# wuBaseV1_4PH.net
KiCad netlist of a schematic drawn in EAGLE
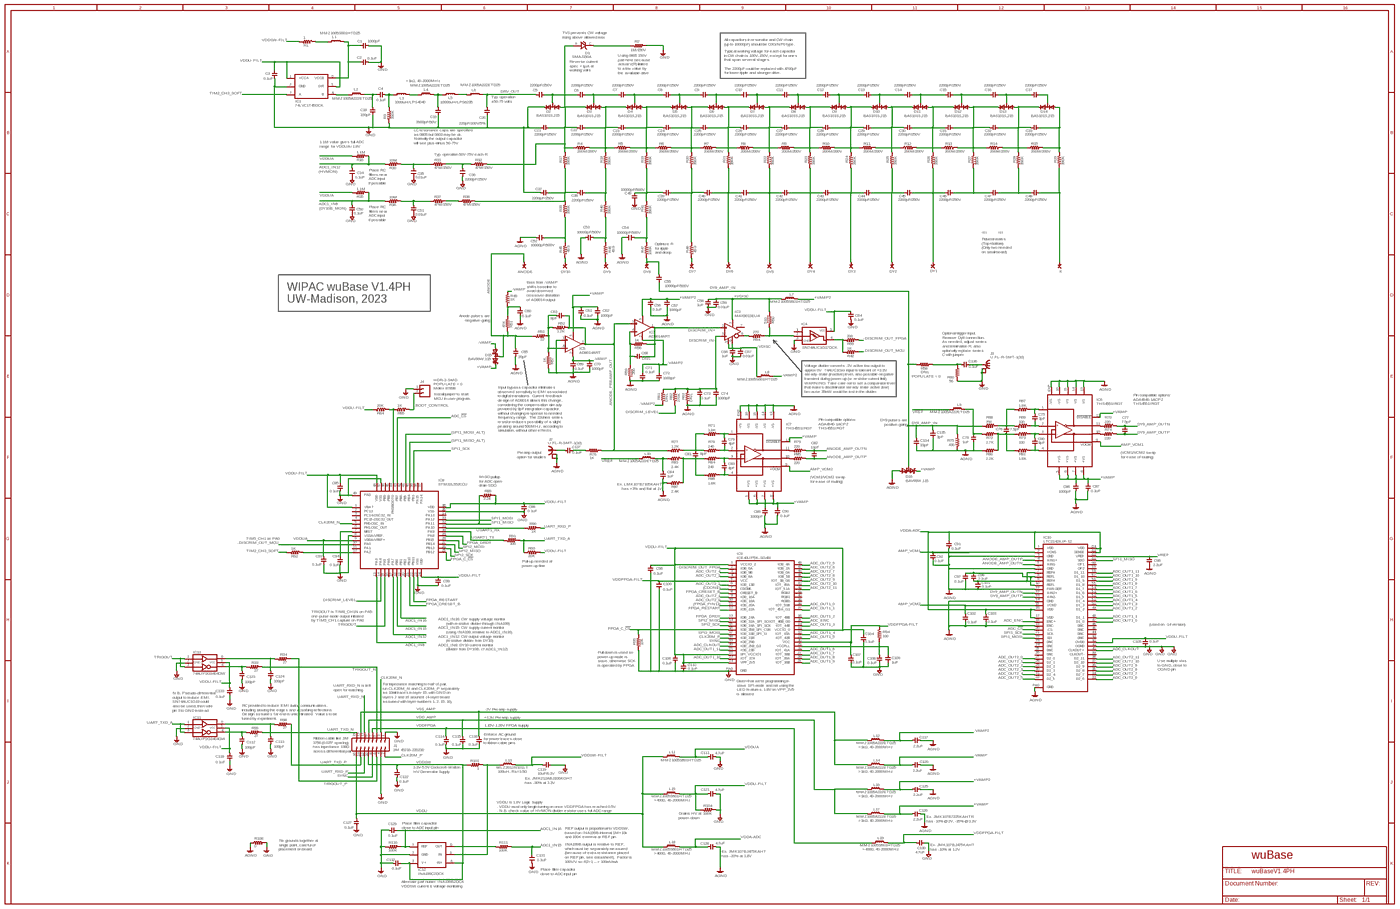
[diagram p0: schematic, sheet 1, overview]
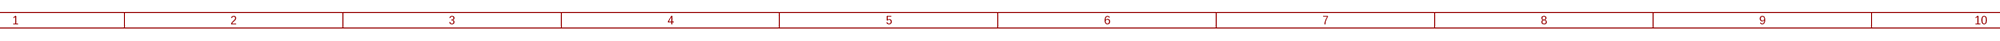
[diagram p1: schematic, sheet 1, part 1 of 4]
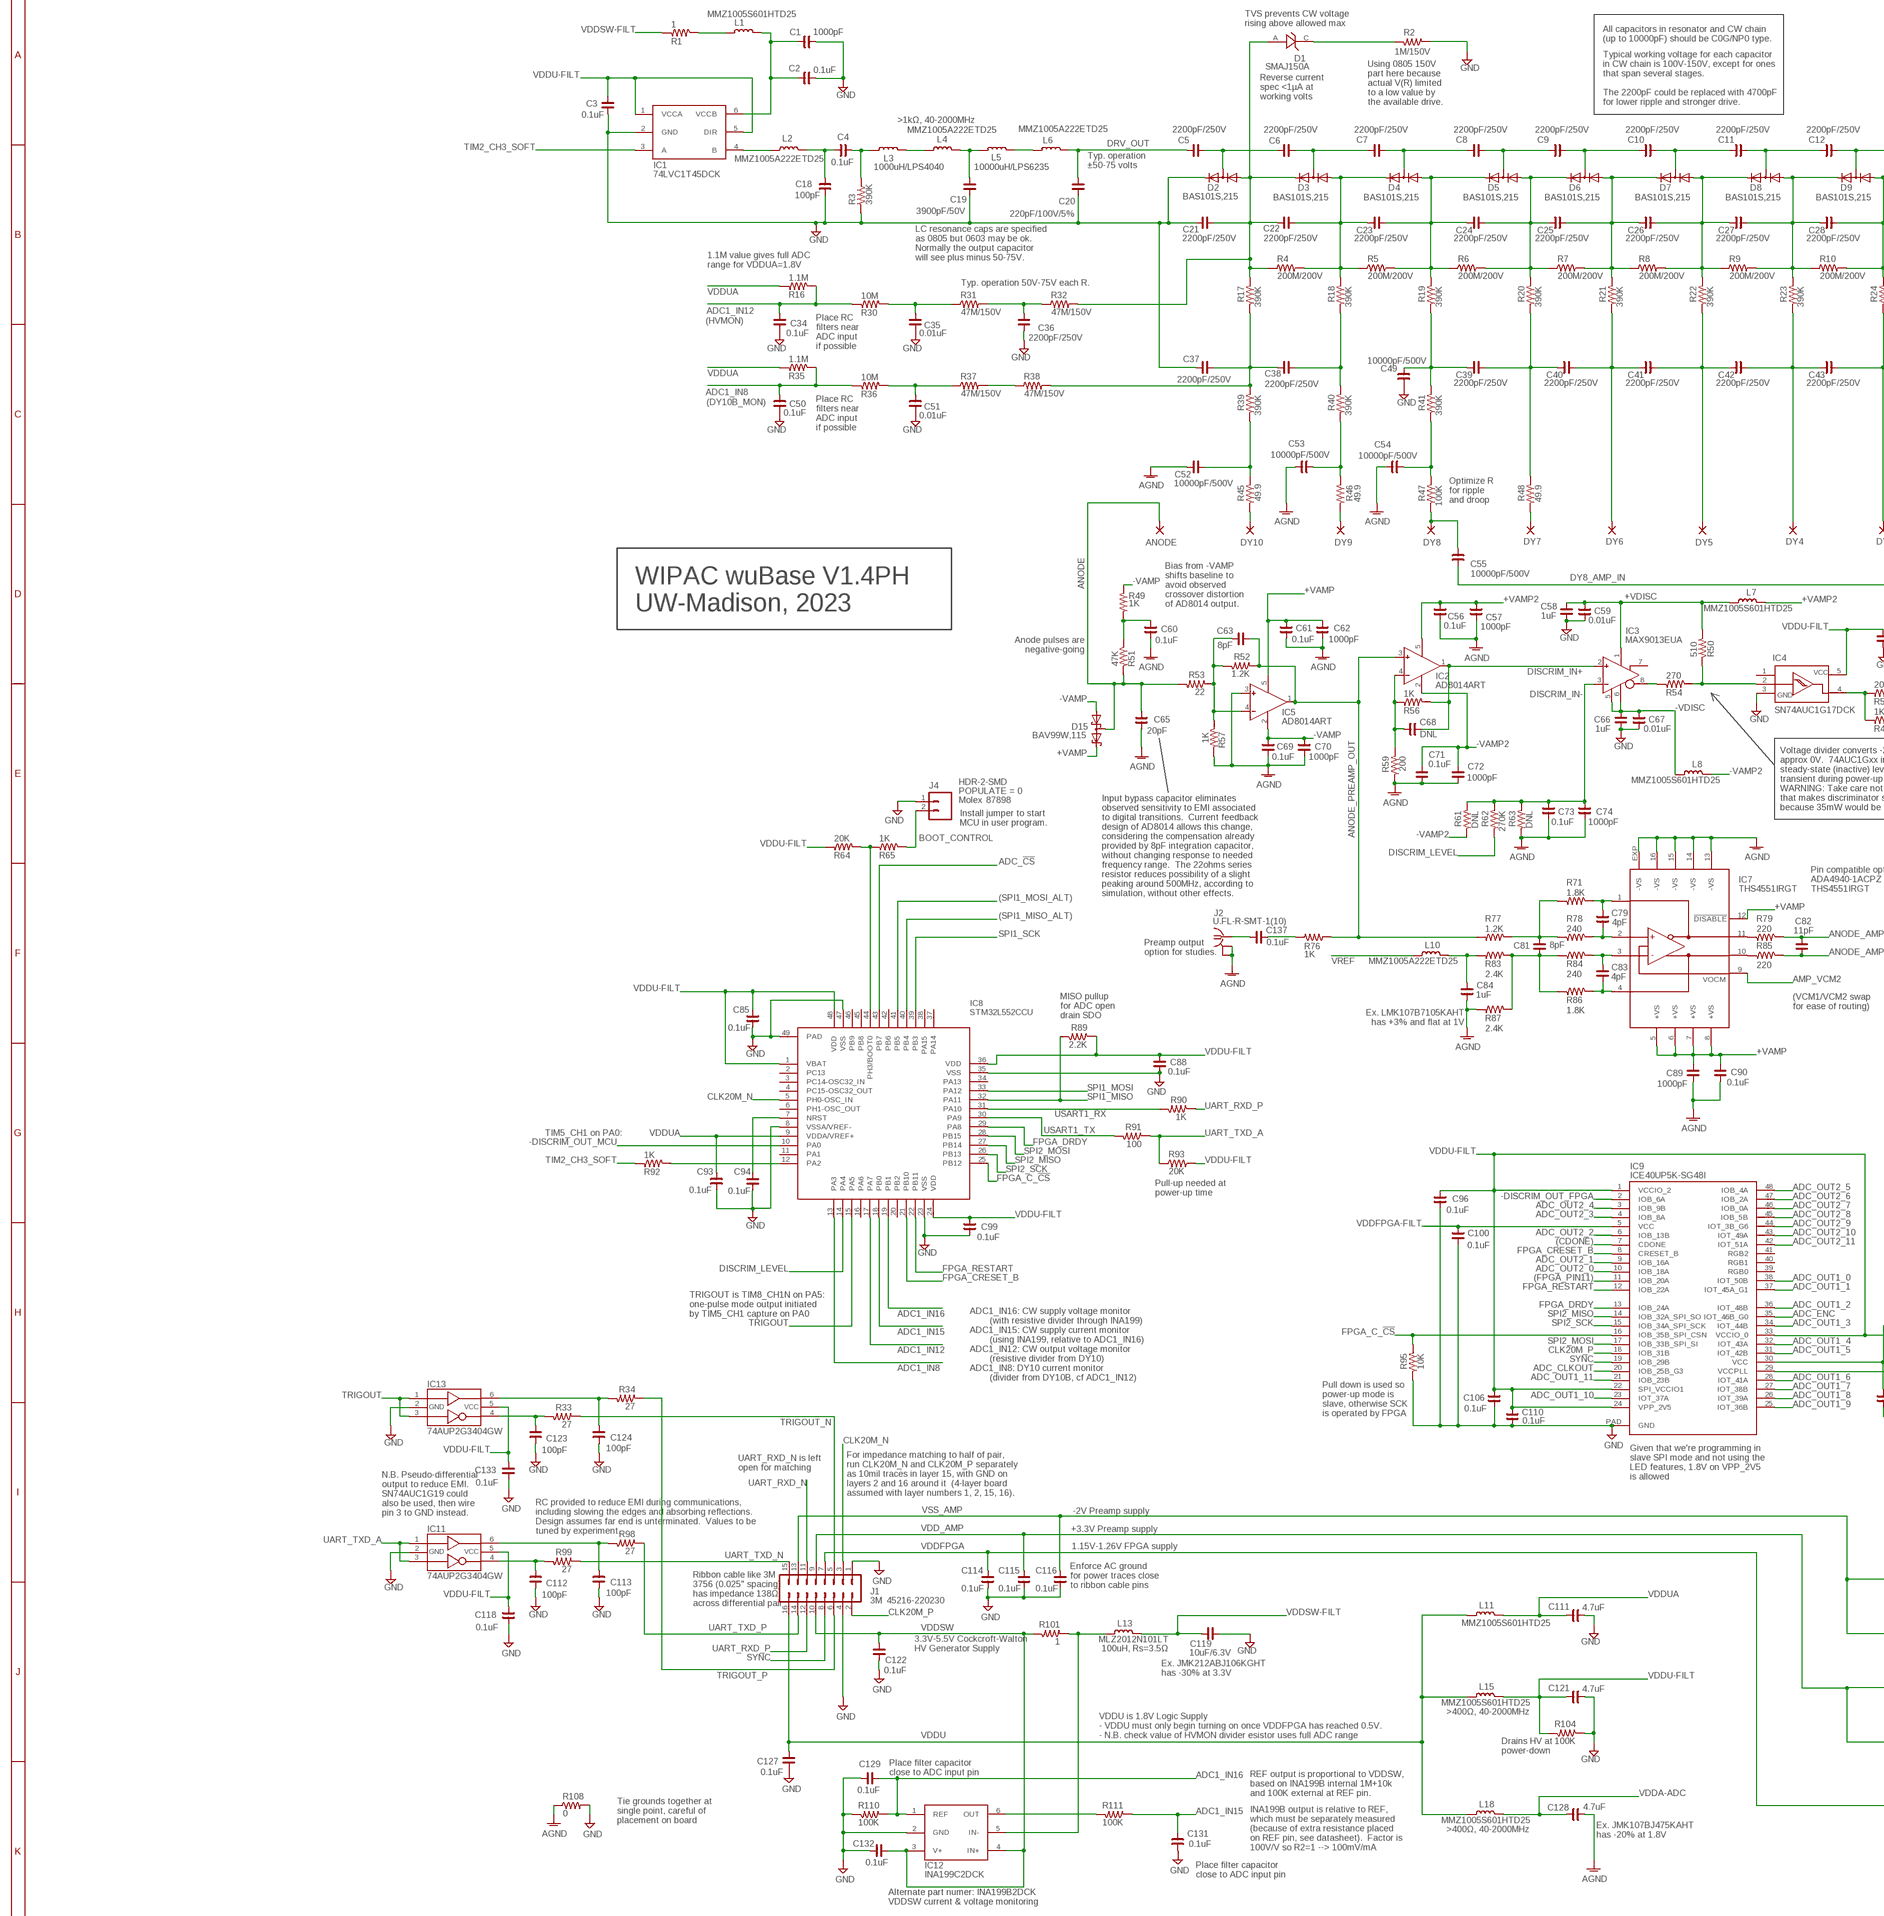
[diagram p2: schematic, sheet 1, part 2 of 4]
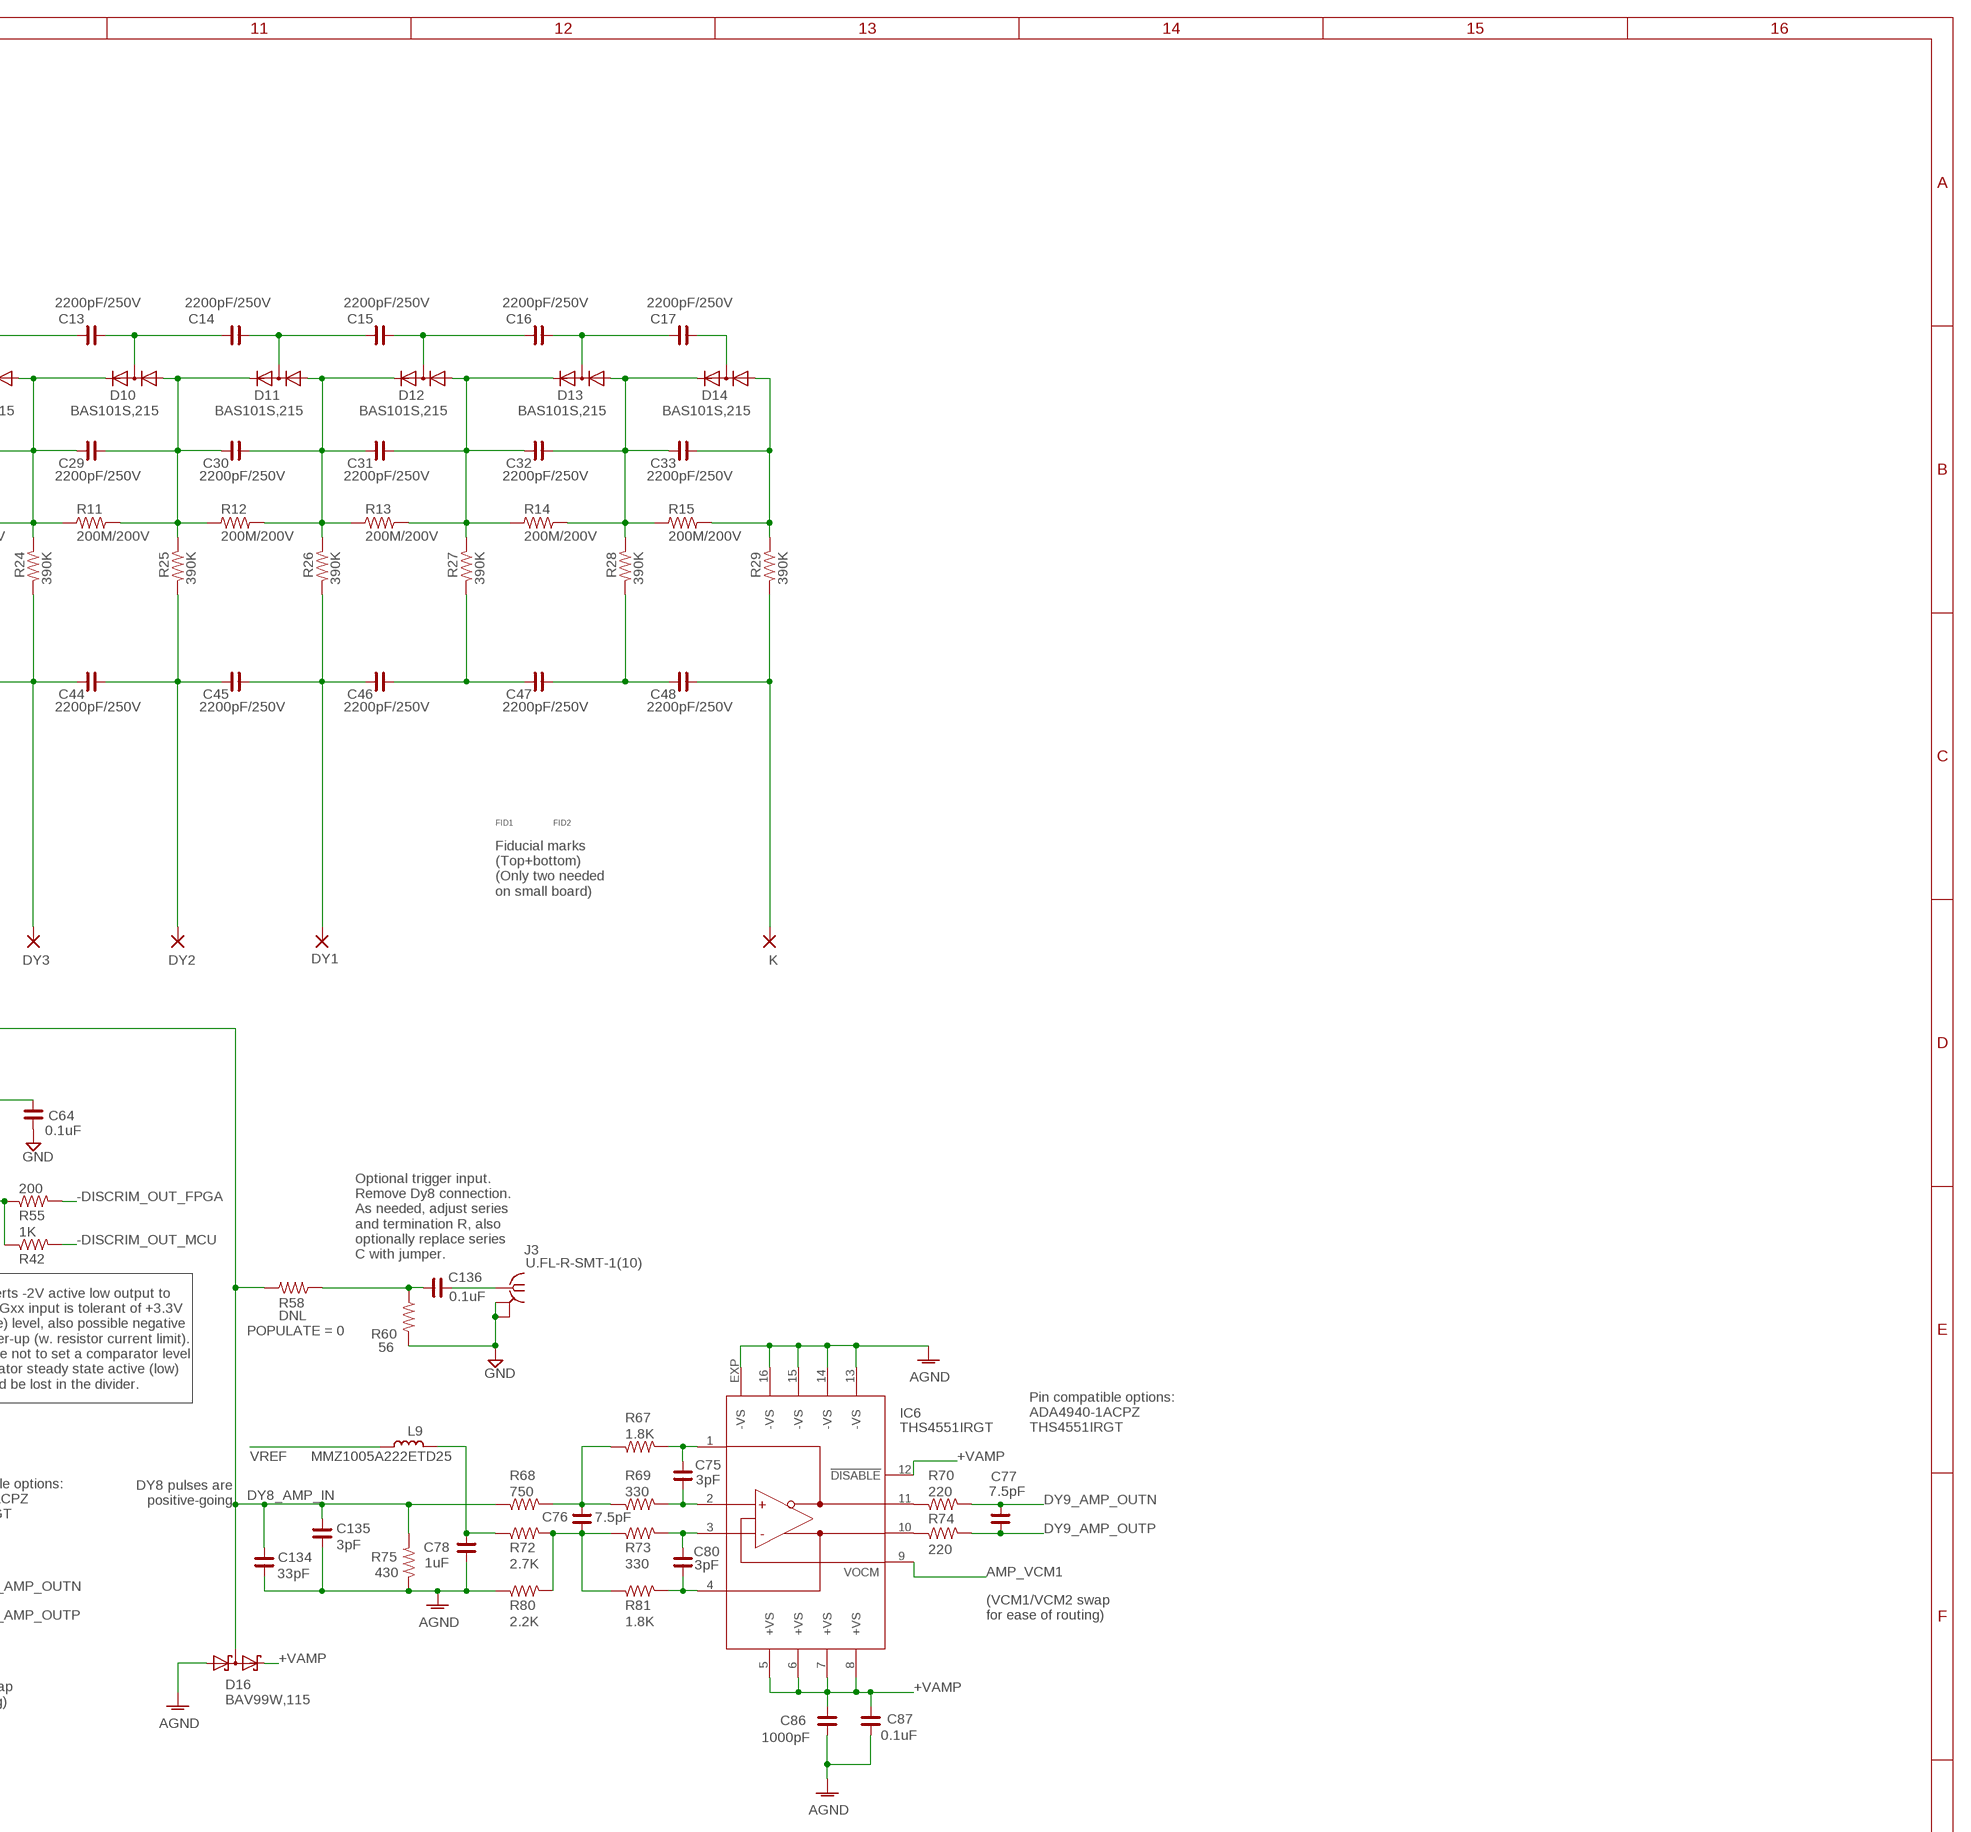
[diagram p3: schematic, sheet 1, part 3 of 4]
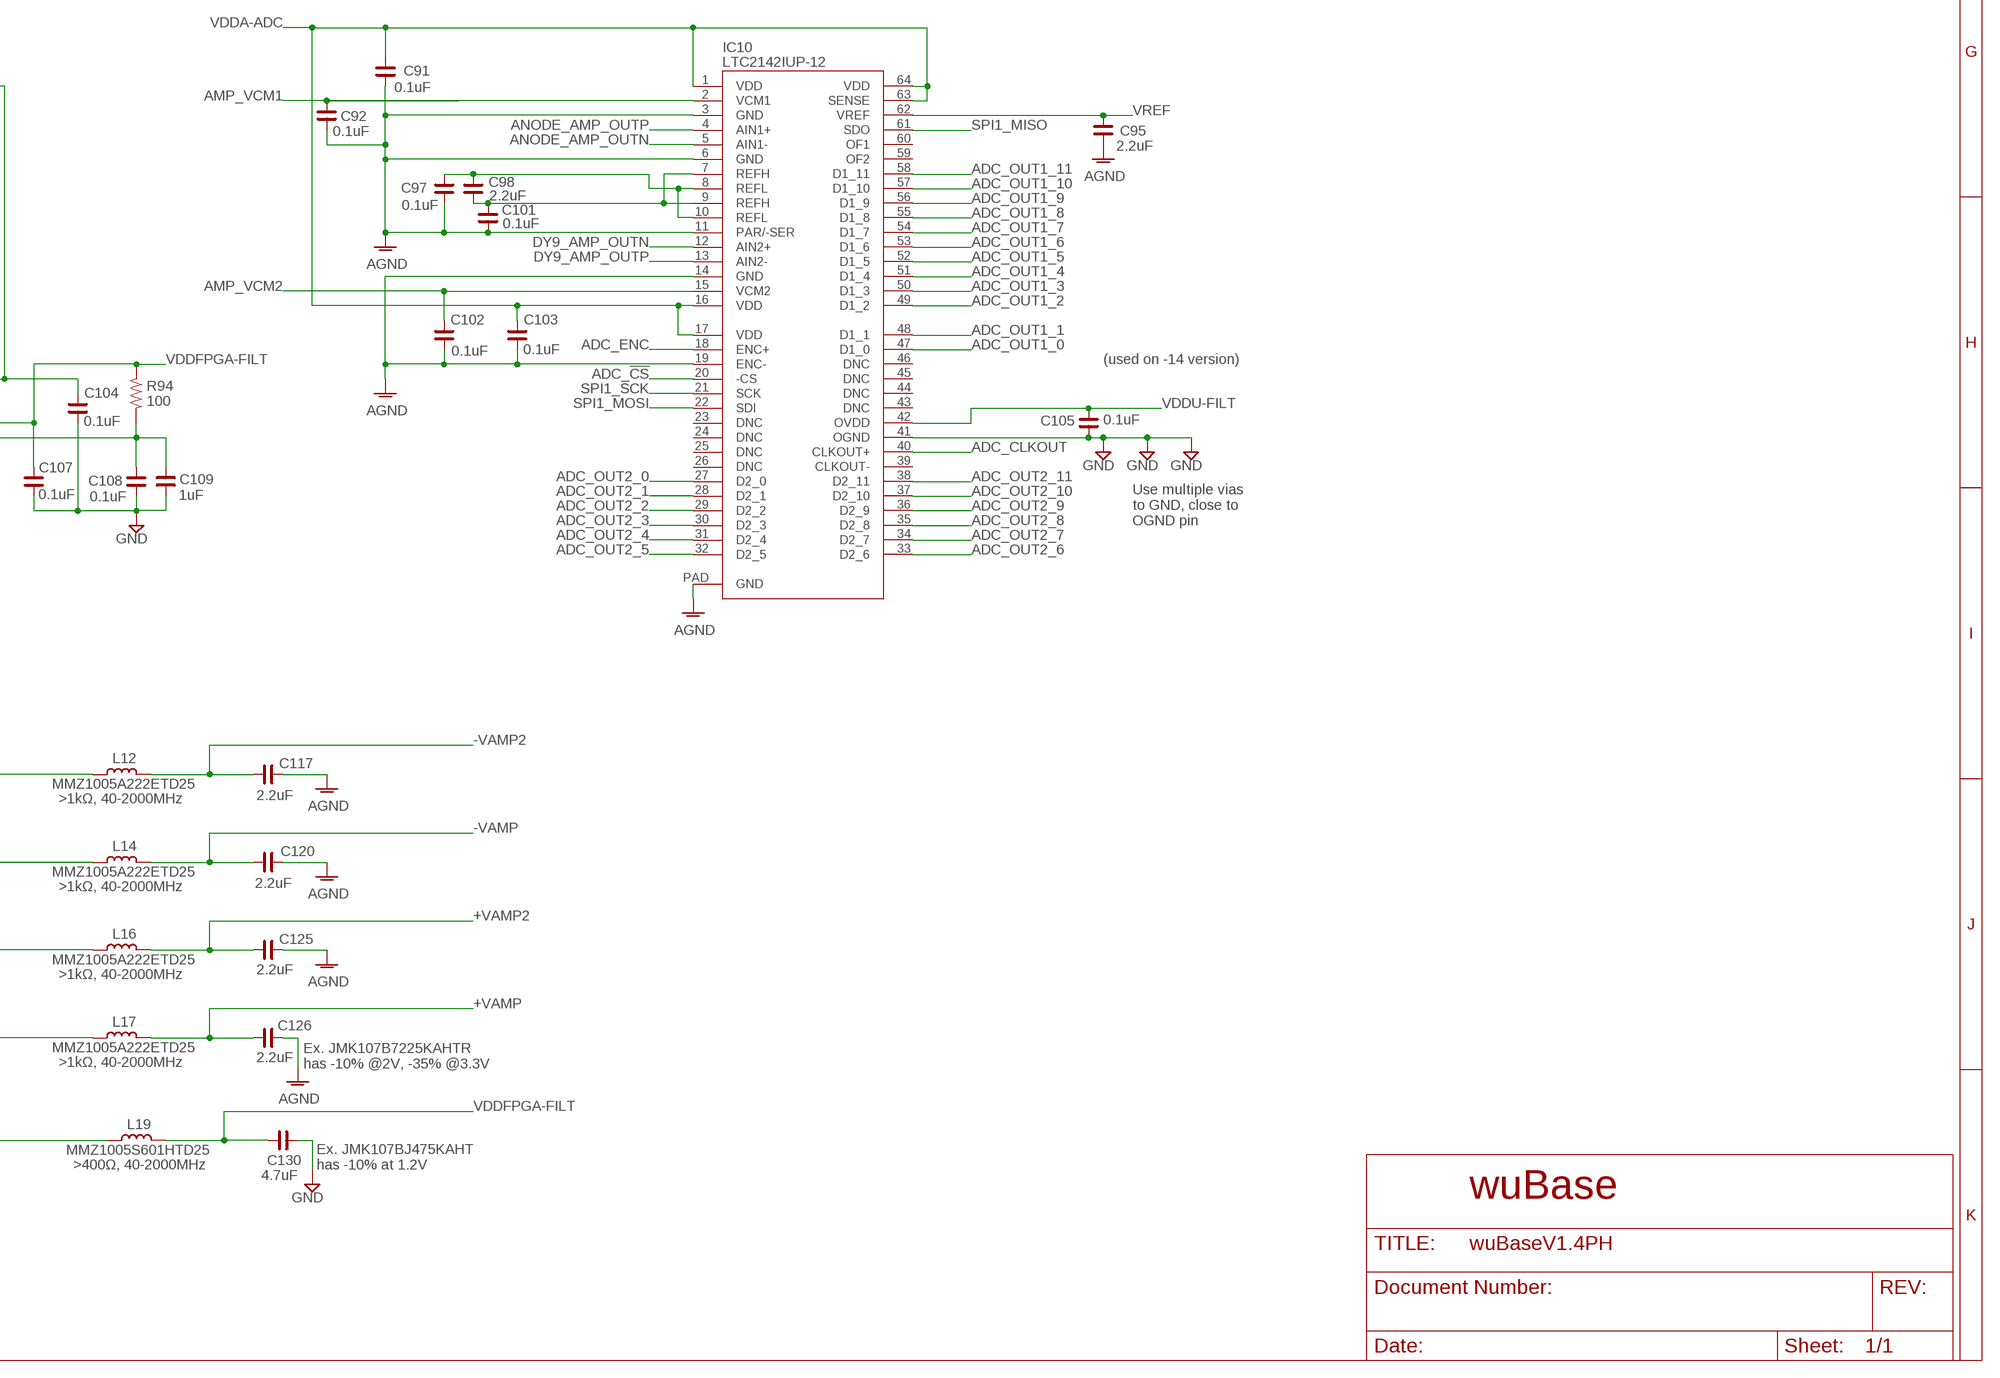
[diagram p4: schematic, sheet 1, part 4 of 4]

(export (version "E")
  (design (tool "Eeschema 10.0.6"))
  (components
    (comp (ref "ANODE")
      (value "PAD-0430-BARE")
      (footprint "eagle-import:0430-BARE")
      (libsource (lib "eagle-import") (part "PAD-0430-BARE"))
    )
    (comp (ref "C1")
      (value "1000pF")
      (footprint "eagle-import:C0402")
      (fields (field (name "MPN") "GCM155R71H102KA37D"))
      (libsource (lib "eagle-import") (part "C_0402"))
    )
    (comp (ref "C2")
      (value "0.1uF")
      (footprint "eagle-import:C0402")
      (fields (field (name "MPN") "GCM155R71C104KA55D"))
      (libsource (lib "eagle-import") (part "C_0402"))
    )
    (comp (ref "C3")
      (value "0.1uF")
      (footprint "eagle-import:C0402")
      (fields (field (name "MPN") "GCM155R71C104KA55D"))
      (libsource (lib "eagle-import") (part "C_0402"))
    )
    (comp (ref "C4")
      (value "0.1uF")
      (footprint "eagle-import:C0402-HV")
      (fields (field (name "MPN") "GCM155R71C104KA55D"))
      (libsource (lib "eagle-import") (part "C_0402HV"))
    )
    (comp (ref "C5")
      (value "2200pF/250V")
      (footprint "eagle-import:C0805-HV")
      (fields (field (name "MPN") "C0805C222JAGACAUTO"))
      (libsource (lib "eagle-import") (part "C_0805HV"))
    )
    (comp (ref "C6")
      (value "2200pF/250V")
      (footprint "eagle-import:C0805-HV")
      (fields (field (name "MPN") "C0805C222JAGACAUTO"))
      (libsource (lib "eagle-import") (part "C_0805HV"))
    )
    (comp (ref "C7")
      (value "2200pF/250V")
      (footprint "eagle-import:C0805-HV")
      (fields (field (name "MPN") "C0805C222JAGACAUTO"))
      (libsource (lib "eagle-import") (part "C_0805HV"))
    )
    (comp (ref "C8")
      (value "2200pF/250V")
      (footprint "eagle-import:C0805-HV")
      (fields (field (name "MPN") "C0805C222JAGACAUTO"))
      (libsource (lib "eagle-import") (part "C_0805HV"))
    )
    (comp (ref "C9")
      (value "2200pF/250V")
      (footprint "eagle-import:C0805-HV")
      (fields (field (name "MPN") "C0805C222JAGACAUTO"))
      (libsource (lib "eagle-import") (part "C_0805HV"))
    )
    (comp (ref "C10")
      (value "2200pF/250V")
      (footprint "eagle-import:C0805-HV")
      (fields (field (name "MPN") "C0805C222JAGACAUTO"))
      (libsource (lib "eagle-import") (part "C_0805HV"))
    )
    (comp (ref "C11")
      (value "2200pF/250V")
      (footprint "eagle-import:C0805-HV")
      (fields (field (name "MPN") "C0805C222JAGACAUTO"))
      (libsource (lib "eagle-import") (part "C_0805HV"))
    )
    (comp (ref "C12")
      (value "2200pF/250V")
      (footprint "eagle-import:C0805-HV")
      (fields (field (name "MPN") "C0805C222JAGACAUTO"))
      (libsource (lib "eagle-import") (part "C_0805HV"))
    )
    (comp (ref "C13")
      (value "2200pF/250V")
      (footprint "eagle-import:C0805-HV")
      (fields (field (name "MPN") "C0805C222JAGACAUTO"))
      (libsource (lib "eagle-import") (part "C_0805HV"))
    )
    (comp (ref "C14")
      (value "2200pF/250V")
      (footprint "eagle-import:C0805-HV")
      (fields (field (name "MPN") "C0805C222JAGACAUTO"))
      (libsource (lib "eagle-import") (part "C_0805HV"))
    )
    (comp (ref "C15")
      (value "2200pF/250V")
      (footprint "eagle-import:C0805-HV")
      (fields (field (name "MPN") "C0805C222JAGACAUTO"))
      (libsource (lib "eagle-import") (part "C_0805HV"))
    )
    (comp (ref "C16")
      (value "2200pF/250V")
      (footprint "eagle-import:C0805-HV")
      (fields (field (name "MPN") "C0805C222JAGACAUTO"))
      (libsource (lib "eagle-import") (part "C_0805HV"))
    )
    (comp (ref "C17")
      (value "2200pF/250V")
      (footprint "eagle-import:C0805-HV")
      (fields (field (name "MPN") "C0805C222JAGACAUTO"))
      (libsource (lib "eagle-import") (part "C_0805HV"))
    )
    (comp (ref "C18")
      (value "100pF")
      (footprint "eagle-import:C0402-HV")
      (fields (field (name "MPN") "C0402C101J3GACAUTO"))
      (libsource (lib "eagle-import") (part "C_0402HV"))
    )
    (comp (ref "C19")
      (value "3900pF/50V")
      (footprint "eagle-import:C0805-HV")
      (fields (field (name "MPN") "CGA4C2C0G1H392J060AA"))
      (libsource (lib "eagle-import") (part "C_0805HV"))
    )
    (comp (ref "C20")
      (value "220pF/100V/5%")
      (footprint "eagle-import:C0805-HV")
      (fields (field (name "MPN") "C0805C221J1GACAUTO"))
      (libsource (lib "eagle-import") (part "C_0805HV"))
    )
    (comp (ref "C21")
      (value "2200pF/250V")
      (footprint "eagle-import:C0805-HV")
      (fields (field (name "MPN") "C0805C222JAGACAUTO"))
      (libsource (lib "eagle-import") (part "C_0805HV"))
    )
    (comp (ref "C22")
      (value "2200pF/250V")
      (footprint "eagle-import:C0805-HV")
      (fields (field (name "MPN") "C0805C222JAGACAUTO"))
      (libsource (lib "eagle-import") (part "C_0805HV"))
    )
    (comp (ref "C23")
      (value "2200pF/250V")
      (footprint "eagle-import:C0805-HV")
      (fields (field (name "MPN") "C0805C222JAGACAUTO"))
      (libsource (lib "eagle-import") (part "C_0805HV"))
    )
    (comp (ref "C24")
      (value "2200pF/250V")
      (footprint "eagle-import:C0805-HV")
      (fields (field (name "MPN") "C0805C222JAGACAUTO"))
      (libsource (lib "eagle-import") (part "C_0805HV"))
    )
    (comp (ref "C25")
      (value "2200pF/250V")
      (footprint "eagle-import:C0805-HV")
      (fields (field (name "MPN") "C0805C222JAGACAUTO"))
      (libsource (lib "eagle-import") (part "C_0805HV"))
    )
    (comp (ref "C26")
      (value "2200pF/250V")
      (footprint "eagle-import:C0805-HV")
      (fields (field (name "MPN") "C0805C222JAGACAUTO"))
      (libsource (lib "eagle-import") (part "C_0805HV"))
    )
    (comp (ref "C27")
      (value "2200pF/250V")
      (footprint "eagle-import:C0805-HV")
      (fields (field (name "MPN") "C0805C222JAGACAUTO"))
      (libsource (lib "eagle-import") (part "C_0805HV"))
    )
    (comp (ref "C28")
      (value "2200pF/250V")
      (footprint "eagle-import:C0805-HV")
      (fields (field (name "MPN") "C0805C222JAGACAUTO"))
      (libsource (lib "eagle-import") (part "C_0805HV"))
    )
    (comp (ref "C29")
      (value "2200pF/250V")
      (footprint "eagle-import:C0805-HV")
      (fields (field (name "MPN") "C0805C222JAGACAUTO"))
      (libsource (lib "eagle-import") (part "C_0805HV"))
    )
    (comp (ref "C30")
      (value "2200pF/250V")
      (footprint "eagle-import:C0805-HV")
      (fields (field (name "MPN") "C0805C222JAGACAUTO"))
      (libsource (lib "eagle-import") (part "C_0805HV"))
    )
    (comp (ref "C31")
      (value "2200pF/250V")
      (footprint "eagle-import:C0805-HV")
      (fields (field (name "MPN") "C0805C222JAGACAUTO"))
      (libsource (lib "eagle-import") (part "C_0805HV"))
    )
    (comp (ref "C32")
      (value "2200pF/250V")
      (footprint "eagle-import:C0805-HV")
      (fields (field (name "MPN") "C0805C222JAGACAUTO"))
      (libsource (lib "eagle-import") (part "C_0805HV"))
    )
    (comp (ref "C33")
      (value "2200pF/250V")
      (footprint "eagle-import:C0805-HV")
      (fields (field (name "MPN") "C0805C222JAGACAUTO"))
      (libsource (lib "eagle-import") (part "C_0805HV"))
    )
    (comp (ref "C34")
      (value "0.1uF")
      (footprint "eagle-import:C0402")
      (fields (field (name "MPN") "GCM155R71C104KA55D"))
      (libsource (lib "eagle-import") (part "C_0402"))
    )
    (comp (ref "C35")
      (value "0.01uF")
      (footprint "eagle-import:C0402")
      (fields (field (name "MPN") "CGA2B2X5R1E103K050BA"))
      (libsource (lib "eagle-import") (part "C_0402"))
    )
    (comp (ref "C36")
      (value "2200pF/250V")
      (footprint "eagle-import:C0805-HV")
      (fields (field (name "MPN") "C0805C222JAGACAUTO"))
      (libsource (lib "eagle-import") (part "C_0805HV"))
    )
    (comp (ref "C37")
      (value "2200pF/250V")
      (footprint "eagle-import:C0805-HV")
      (fields (field (name "MPN") "C0805C222JAGACAUTO"))
      (libsource (lib "eagle-import") (part "C_0805HV"))
    )
    (comp (ref "C38")
      (value "2200pF/250V")
      (footprint "eagle-import:C0805-HV")
      (fields (field (name "MPN") "C0805C222JAGACAUTO"))
      (libsource (lib "eagle-import") (part "C_0805HV"))
    )
    (comp (ref "C39")
      (value "2200pF/250V")
      (footprint "eagle-import:C0805-HV")
      (fields (field (name "MPN") "C0805C222JAGACAUTO"))
      (libsource (lib "eagle-import") (part "C_0805HV"))
    )
    (comp (ref "C40")
      (value "2200pF/250V")
      (footprint "eagle-import:C0805-HV")
      (fields (field (name "MPN") "C0805C222JAGACAUTO"))
      (libsource (lib "eagle-import") (part "C_0805HV"))
    )
    (comp (ref "C41")
      (value "2200pF/250V")
      (footprint "eagle-import:C0805-HV")
      (fields (field (name "MPN") "C0805C222JAGACAUTO"))
      (libsource (lib "eagle-import") (part "C_0805HV"))
    )
    (comp (ref "C42")
      (value "2200pF/250V")
      (footprint "eagle-import:C0805-HV")
      (fields (field (name "MPN") "C0805C222JAGACAUTO"))
      (libsource (lib "eagle-import") (part "C_0805HV"))
    )
    (comp (ref "C43")
      (value "2200pF/250V")
      (footprint "eagle-import:C0805-HV")
      (fields (field (name "MPN") "C0805C222JAGACAUTO"))
      (libsource (lib "eagle-import") (part "C_0805HV"))
    )
    (comp (ref "C44")
      (value "2200pF/250V")
      (footprint "eagle-import:C0805-HV")
      (fields (field (name "MPN") "C0805C222JAGACAUTO"))
      (libsource (lib "eagle-import") (part "C_0805HV"))
    )
    (comp (ref "C45")
      (value "2200pF/250V")
      (footprint "eagle-import:C0805-HV")
      (fields (field (name "MPN") "C0805C222JAGACAUTO"))
      (libsource (lib "eagle-import") (part "C_0805HV"))
    )
    (comp (ref "C46")
      (value "2200pF/250V")
      (footprint "eagle-import:C0805-HV")
      (fields (field (name "MPN") "C0805C222JAGACAUTO"))
      (libsource (lib "eagle-import") (part "C_0805HV"))
    )
    (comp (ref "C47")
      (value "2200pF/250V")
      (footprint "eagle-import:C0805-HV")
      (fields (field (name "MPN") "C0805C222JAGACAUTO"))
      (libsource (lib "eagle-import") (part "C_0805HV"))
    )
    (comp (ref "C48")
      (value "2200pF/250V")
      (footprint "eagle-import:C0805-HV")
      (fields (field (name "MPN") "C0805C222JAGACAUTO"))
      (libsource (lib "eagle-import") (part "C_0805HV"))
    )
    (comp (ref "C49")
      (value "10000pF/500V")
      (footprint "eagle-import:C1206-HV")
      (fields (field (name "MPN") "CGA5L4NP02J103J160AA"))
      (libsource (lib "eagle-import") (part "C_1206HV"))
    )
    (comp (ref "C50")
      (value "0.1uF")
      (footprint "eagle-import:C0402")
      (fields (field (name "MPN") "GCM155R71C104KA55D"))
      (libsource (lib "eagle-import") (part "C_0402"))
    )
    (comp (ref "C51")
      (value "0.01uF")
      (footprint "eagle-import:C0402")
      (fields (field (name "MPN") "CGA2B2X5R1E103K050BA"))
      (libsource (lib "eagle-import") (part "C_0402"))
    )
    (comp (ref "C52")
      (value "10000pF/500V")
      (footprint "eagle-import:C1206-HV")
      (fields (field (name "MPN") "CGA5L4NP02J103J160AA"))
      (libsource (lib "eagle-import") (part "C_1206HV"))
    )
    (comp (ref "C53")
      (value "10000pF/500V")
      (footprint "eagle-import:C1206-HV")
      (fields (field (name "MPN") "CGA5L4NP02J103J160AA"))
      (libsource (lib "eagle-import") (part "C_1206HV"))
    )
    (comp (ref "C54")
      (value "10000pF/500V")
      (footprint "eagle-import:C1206-HV")
      (fields (field (name "MPN") "CGA5L4NP02J103J160AA"))
      (libsource (lib "eagle-import") (part "C_1206HV"))
    )
    (comp (ref "C55")
      (value "10000pF/500V")
      (footprint "eagle-import:C1206-HV")
      (fields (field (name "MPN") "CGA5L4NP02J103J160AA"))
      (libsource (lib "eagle-import") (part "C_1206HV"))
    )
    (comp (ref "C56")
      (value "0.1uF")
      (footprint "eagle-import:C0402")
      (fields (field (name "MPN") "GCM155R71C104KA55D"))
      (libsource (lib "eagle-import") (part "C_0402"))
    )
    (comp (ref "C57")
      (value "1000pF")
      (footprint "eagle-import:C0402")
      (fields (field (name "MPN") "GCM155R71H102KA37D"))
      (libsource (lib "eagle-import") (part "C_0402"))
    )
    (comp (ref "C58")
      (value "1uF")
      (footprint "eagle-import:C0603")
      (fields (field (name "MPN") "LMK107B7105KAHT"))
      (libsource (lib "eagle-import") (part "C_0603"))
    )
    (comp (ref "C59")
      (value "0.01uF")
      (footprint "eagle-import:C0402")
      (fields (field (name "MPN") "CGA2B2X5R1E103K050BA"))
      (libsource (lib "eagle-import") (part "C_0402"))
    )
    (comp (ref "C60")
      (value "0.1uF")
      (footprint "eagle-import:C0402")
      (fields (field (name "MPN") "GCM155R71C104KA55D"))
      (libsource (lib "eagle-import") (part "C_0402"))
    )
    (comp (ref "C61")
      (value "0.1uF")
      (footprint "eagle-import:C0402")
      (fields (field (name "MPN") "GCM155R71C104KA55D"))
      (libsource (lib "eagle-import") (part "C_0402"))
    )
    (comp (ref "C62")
      (value "1000pF")
      (footprint "eagle-import:C0402")
      (fields (field (name "MPN") "GCM155R71H102KA37D"))
      (libsource (lib "eagle-import") (part "C_0402"))
    )
    (comp (ref "C63")
      (value "8pF")
      (footprint "eagle-import:C0402")
      (fields (field (name "MPN") "GCM1555C1H8R0BA16D"))
      (libsource (lib "eagle-import") (part "C_0402"))
    )
    (comp (ref "C64")
      (value "0.1uF")
      (footprint "eagle-import:C0402")
      (fields (field (name "MPN") "GCM155R71C104KA55D"))
      (libsource (lib "eagle-import") (part "C_0402"))
    )
    (comp (ref "C65")
      (value "20pF")
      (footprint "eagle-import:C0402")
      (fields (field (name "MPN") "GCM1555C1H200JA16D"))
      (libsource (lib "eagle-import") (part "C_0402"))
    )
    (comp (ref "C66")
      (value "1uF")
      (footprint "eagle-import:C0603")
      (fields (field (name "MPN") "LMK107B7105KAHT"))
      (libsource (lib "eagle-import") (part "C_0603"))
    )
    (comp (ref "C67")
      (value "0.01uF")
      (footprint "eagle-import:C0402")
      (fields (field (name "MPN") "CGA2B2X5R1E103K050BA"))
      (libsource (lib "eagle-import") (part "C_0402"))
    )
    (comp (ref "C68")
      (value "DNL")
      (footprint "eagle-import:C0402")
      (fields (field (name "POPULATE") "0"))
      (libsource (lib "eagle-import") (part "C_0402"))
    )
    (comp (ref "C69")
      (value "0.1uF")
      (footprint "eagle-import:C0402")
      (fields (field (name "MPN") "GCM155R71C104KA55D"))
      (libsource (lib "eagle-import") (part "C_0402"))
    )
    (comp (ref "C70")
      (value "1000pF")
      (footprint "eagle-import:C0402")
      (fields (field (name "MPN") "GCM155R71H102KA37D"))
      (libsource (lib "eagle-import") (part "C_0402"))
    )
    (comp (ref "C71")
      (value "0.1uF")
      (footprint "eagle-import:C0402")
      (fields (field (name "MPN") "GCM155R71C104KA55D"))
      (libsource (lib "eagle-import") (part "C_0402"))
    )
    (comp (ref "C72")
      (value "1000pF")
      (footprint "eagle-import:C0402")
      (fields (field (name "MPN") "GCM155R71H102KA37D"))
      (libsource (lib "eagle-import") (part "C_0402"))
    )
    (comp (ref "C73")
      (value "0.1uF")
      (footprint "eagle-import:C0402")
      (fields (field (name "MPN") "GCM155R71C104KA55D"))
      (libsource (lib "eagle-import") (part "C_0402"))
    )
    (comp (ref "C74")
      (value "1000pF")
      (footprint "eagle-import:C0402")
      (fields (field (name "MPN") "GCM155R71H102KA37D"))
      (libsource (lib "eagle-import") (part "C_0402"))
    )
    (comp (ref "C75")
      (value "3pF")
      (footprint "eagle-import:C0402")
      (fields (field (name "MPN") "GCM1555C1H3R0BA16D"))
      (libsource (lib "eagle-import") (part "C_0402"))
    )
    (comp (ref "C76")
      (value "7.5pF")
      (footprint "eagle-import:C0402")
      (fields (field (name "MPN") "GCQ1555C1H7R5BB01D"))
      (libsource (lib "eagle-import") (part "C_0402"))
    )
    (comp (ref "C77")
      (value "7.5pF")
      (footprint "eagle-import:C0402")
      (fields (field (name "MPN") "GCQ1555C1H7R5BB01D"))
      (libsource (lib "eagle-import") (part "C_0402"))
    )
    (comp (ref "C78")
      (value "1uF")
      (footprint "eagle-import:C0603")
      (fields (field (name "MPN") "LMK107B7105KAHT"))
      (libsource (lib "eagle-import") (part "C_0603"))
    )
    (comp (ref "C79")
      (value "4pF")
      (footprint "eagle-import:C0402")
      (fields (field (name "MPN") "GCM1555C1H4R0BA16D"))
      (libsource (lib "eagle-import") (part "C_0402"))
    )
    (comp (ref "C80")
      (value "3pF")
      (footprint "eagle-import:C0402")
      (fields (field (name "MPN") "GCM1555C1H3R0BA16D"))
      (libsource (lib "eagle-import") (part "C_0402"))
    )
    (comp (ref "C81")
      (value "8pF")
      (footprint "eagle-import:C0402")
      (fields (field (name "MPN") "GCM1555C1H8R0BA16D"))
      (libsource (lib "eagle-import") (part "C_0402"))
    )
    (comp (ref "C82")
      (value "11pF")
      (footprint "eagle-import:C0402")
      (fields (field (name "MPN") "GCM1555C1H110FA16D"))
      (libsource (lib "eagle-import") (part "C_0402"))
    )
    (comp (ref "C83")
      (value "4pF")
      (footprint "eagle-import:C0402")
      (fields (field (name "MPN") "GCM1555C1H4R0BA16D"))
      (libsource (lib "eagle-import") (part "C_0402"))
    )
    (comp (ref "C84")
      (value "1uF")
      (footprint "eagle-import:C0603")
      (fields (field (name "MPN") "LMK107B7105KAHT"))
      (libsource (lib "eagle-import") (part "C_0603"))
    )
    (comp (ref "C85")
      (value "0.1uF")
      (footprint "eagle-import:C0402")
      (fields (field (name "MPN") "GCM155R71C104KA55D"))
      (libsource (lib "eagle-import") (part "C_0402"))
    )
    (comp (ref "C86")
      (value "1000pF")
      (footprint "eagle-import:C0402")
      (fields (field (name "MPN") "GCM155R71H102KA37D"))
      (libsource (lib "eagle-import") (part "C_0402"))
    )
    (comp (ref "C87")
      (value "0.1uF")
      (footprint "eagle-import:C0402")
      (fields (field (name "MPN") "GCM155R71C104KA55D"))
      (libsource (lib "eagle-import") (part "C_0402"))
    )
    (comp (ref "C88")
      (value "0.1uF")
      (footprint "eagle-import:C0402")
      (fields (field (name "MPN") "GCM155R71C104KA55D"))
      (libsource (lib "eagle-import") (part "C_0402"))
    )
    (comp (ref "C89")
      (value "1000pF")
      (footprint "eagle-import:C0402")
      (fields (field (name "MPN") "GCM155R71H102KA37D"))
      (libsource (lib "eagle-import") (part "C_0402"))
    )
    (comp (ref "C90")
      (value "0.1uF")
      (footprint "eagle-import:C0402")
      (fields (field (name "MPN") "GCM155R71C104KA55D"))
      (libsource (lib "eagle-import") (part "C_0402"))
    )
    (comp (ref "C91")
      (value "0.1uF")
      (footprint "eagle-import:C0402")
      (fields (field (name "MPN") "GCM155R71C104KA55D"))
      (libsource (lib "eagle-import") (part "C_0402"))
    )
    (comp (ref "C92")
      (value "0.1uF")
      (footprint "eagle-import:C0402")
      (fields (field (name "MPN") "GCM155R71C104KA55D"))
      (libsource (lib "eagle-import") (part "C_0402"))
    )
    (comp (ref "C93")
      (value "0.1uF")
      (footprint "eagle-import:C0402")
      (fields (field (name "MPN") "GCM155R71C104KA55D"))
      (libsource (lib "eagle-import") (part "C_0402"))
    )
    (comp (ref "C94")
      (value "0.1uF")
      (footprint "eagle-import:C0402")
      (fields (field (name "MPN") "GCM155R71C104KA55D"))
      (libsource (lib "eagle-import") (part "C_0402"))
    )
    (comp (ref "C95")
      (value "2.2uF")
      (footprint "eagle-import:C0603")
      (fields (field (name "MPN") "CGA3E1X7R0J225K080AC"))
      (libsource (lib "eagle-import") (part "C_0603"))
    )
    (comp (ref "C96")
      (value "0.1uF")
      (footprint "eagle-import:C0402")
      (fields (field (name "MPN") "GCM155R71C104KA55D"))
      (libsource (lib "eagle-import") (part "C_0402"))
    )
    (comp (ref "C97")
      (value "0.1uF")
      (footprint "eagle-import:C0402")
      (fields (field (name "MPN") "GCM155R71C104KA55D"))
      (libsource (lib "eagle-import") (part "C_0402"))
    )
    (comp (ref "C98")
      (value "2.2uF")
      (footprint "eagle-import:C0603")
      (fields (field (name "MPN") "CGA3E1X7R0J225K080AC"))
      (libsource (lib "eagle-import") (part "C_0603"))
    )
    (comp (ref "C99")
      (value "0.1uF")
      (footprint "eagle-import:C0402")
      (fields (field (name "MPN") "GCM155R71C104KA55D"))
      (libsource (lib "eagle-import") (part "C_0402"))
    )
    (comp (ref "C100")
      (value "0.1uF")
      (footprint "eagle-import:C0402")
      (fields (field (name "MPN") "GCM155R71C104KA55D"))
      (libsource (lib "eagle-import") (part "C_0402"))
    )
    (comp (ref "C101")
      (value "0.1uF")
      (footprint "eagle-import:C0402")
      (fields (field (name "MPN") "GCM155R71C104KA55D"))
      (libsource (lib "eagle-import") (part "C_0402"))
    )
    (comp (ref "C102")
      (value "0.1uF")
      (footprint "eagle-import:C0402")
      (fields (field (name "MPN") "GCM155R71C104KA55D"))
      (libsource (lib "eagle-import") (part "C_0402"))
    )
    (comp (ref "C103")
      (value "0.1uF")
      (footprint "eagle-import:C0402")
      (fields (field (name "MPN") "GCM155R71C104KA55D"))
      (libsource (lib "eagle-import") (part "C_0402"))
    )
    (comp (ref "C104")
      (value "0.1uF")
      (footprint "eagle-import:C0402")
      (fields (field (name "MPN") "GCM155R71C104KA55D"))
      (libsource (lib "eagle-import") (part "C_0402"))
    )
    (comp (ref "C105")
      (value "0.1uF")
      (footprint "eagle-import:C0402")
      (fields (field (name "MPN") "GCM155R71C104KA55D"))
      (libsource (lib "eagle-import") (part "C_0402"))
    )
    (comp (ref "C106")
      (value "0.1uF")
      (footprint "eagle-import:C0402")
      (fields (field (name "MPN") "GCM155R71C104KA55D"))
      (libsource (lib "eagle-import") (part "C_0402"))
    )
    (comp (ref "C107")
      (value "0.1uF")
      (footprint "eagle-import:C0402")
      (fields (field (name "MPN") "GCM155R71C104KA55D"))
      (libsource (lib "eagle-import") (part "C_0402"))
    )
    (comp (ref "C108")
      (value "0.1uF")
      (footprint "eagle-import:C0402")
      (fields (field (name "MPN") "GCM155R71C104KA55D"))
      (libsource (lib "eagle-import") (part "C_0402"))
    )
    (comp (ref "C109")
      (value "1uF")
      (footprint "eagle-import:C0603")
      (fields (field (name "MPN") "LMK107B7105KAHT"))
      (libsource (lib "eagle-import") (part "C_0603"))
    )
    (comp (ref "C110")
      (value "0.1uF")
      (footprint "eagle-import:C0402")
      (fields (field (name "MPN") "GCM155R71C104KA55D"))
      (libsource (lib "eagle-import") (part "C_0402"))
    )
    (comp (ref "C111")
      (value "4.7uF")
      (footprint "eagle-import:C0603")
      (fields (field (name "MPN") "JMK107BJ475KAHT"))
      (libsource (lib "eagle-import") (part "C_0603"))
    )
    (comp (ref "C112")
      (value "100pF")
      (footprint "eagle-import:C0402")
      (fields (field (name "MPN") "C0402C101J3GACAUTO"))
      (libsource (lib "eagle-import") (part "C_0402"))
    )
    (comp (ref "C113")
      (value "100pF")
      (footprint "eagle-import:C0402")
      (fields (field (name "MPN") "C0402C101J3GACAUTO"))
      (libsource (lib "eagle-import") (part "C_0402"))
    )
    (comp (ref "C114")
      (value "0.1uF")
      (footprint "eagle-import:C0402")
      (fields (field (name "MPN") "GCM155R71C104KA55D"))
      (libsource (lib "eagle-import") (part "C_0402"))
    )
    (comp (ref "C115")
      (value "0.1uF")
      (footprint "eagle-import:C0402")
      (fields (field (name "MPN") "GCM155R71C104KA55D"))
      (libsource (lib "eagle-import") (part "C_0402"))
    )
    (comp (ref "C116")
      (value "0.1uF")
      (footprint "eagle-import:C0402")
      (fields (field (name "MPN") "GCM155R71C104KA55D"))
      (libsource (lib "eagle-import") (part "C_0402"))
    )
    (comp (ref "C117")
      (value "2.2uF")
      (footprint "eagle-import:C0603")
      (fields (field (name "MPN") "CGA3E1X7R0J225K080AC"))
      (libsource (lib "eagle-import") (part "C_0603"))
    )
    (comp (ref "C118")
      (value "0.1uF")
      (footprint "eagle-import:C0402")
      (fields (field (name "MPN") "GCM155R71C104KA55D"))
      (libsource (lib "eagle-import") (part "C_0402"))
    )
    (comp (ref "C119")
      (value "10uF/6.3V")
      (footprint "eagle-import:C0805")
      (fields (field (name "MPN") "C0805C106K8PACTU"))
      (libsource (lib "eagle-import") (part "C_0805"))
    )
    (comp (ref "C120")
      (value "2.2uF")
      (footprint "eagle-import:C0603")
      (fields (field (name "MPN") "CGA3E1X7R0J225K080AC"))
      (libsource (lib "eagle-import") (part "C_0603"))
    )
    (comp (ref "C121")
      (value "4.7uF")
      (footprint "eagle-import:C0603")
      (fields (field (name "MPN") "JMK107BJ475KAHT"))
      (libsource (lib "eagle-import") (part "C_0603"))
    )
    (comp (ref "C122")
      (value "0.1uF")
      (footprint "eagle-import:C0402")
      (fields (field (name "MPN") "GCM155R71C104KA55D"))
      (libsource (lib "eagle-import") (part "C_0402"))
    )
    (comp (ref "C123")
      (value "100pF")
      (footprint "eagle-import:C0402")
      (fields (field (name "MPN") "C0402C101J3GACAUTO"))
      (libsource (lib "eagle-import") (part "C_0402"))
    )
    (comp (ref "C124")
      (value "100pF")
      (footprint "eagle-import:C0402")
      (fields (field (name "MPN") "C0402C101J3GACAUTO"))
      (libsource (lib "eagle-import") (part "C_0402"))
    )
    (comp (ref "C125")
      (value "2.2uF")
      (footprint "eagle-import:C0603")
      (fields (field (name "MPN") "CGA3E1X7R0J225K080AC"))
      (libsource (lib "eagle-import") (part "C_0603"))
    )
    (comp (ref "C126")
      (value "2.2uF")
      (footprint "eagle-import:C0603")
      (fields (field (name "MPN") "CGA3E1X7R0J225K080AC"))
      (libsource (lib "eagle-import") (part "C_0603"))
    )
    (comp (ref "C127")
      (value "0.1uF")
      (footprint "eagle-import:C0402")
      (fields (field (name "MPN") "GCM155R71C104KA55D"))
      (libsource (lib "eagle-import") (part "C_0402"))
    )
    (comp (ref "C128")
      (value "4.7uF")
      (footprint "eagle-import:C0603")
      (fields (field (name "MPN") "JMK107BJ475KAHT"))
      (libsource (lib "eagle-import") (part "C_0603"))
    )
    (comp (ref "C129")
      (value "0.1uF")
      (footprint "eagle-import:C0402")
      (fields (field (name "MPN") "GCM155R71C104KA55D"))
      (libsource (lib "eagle-import") (part "C_0402"))
    )
    (comp (ref "C130")
      (value "4.7uF")
      (footprint "eagle-import:C0603")
      (fields (field (name "MPN") "JMK107BJ475KAHT"))
      (libsource (lib "eagle-import") (part "C_0603"))
    )
    (comp (ref "C131")
      (value "0.1uF")
      (footprint "eagle-import:C0402")
      (fields (field (name "MPN") "GCM155R71C104KA55D"))
      (libsource (lib "eagle-import") (part "C_0402"))
    )
    (comp (ref "C132")
      (value "0.1uF")
      (footprint "eagle-import:C0402")
      (fields (field (name "MPN") "GCM155R71C104KA55D"))
      (libsource (lib "eagle-import") (part "C_0402"))
    )
    (comp (ref "C133")
      (value "0.1uF")
      (footprint "eagle-import:C0402")
      (fields (field (name "MPN") "GCM155R71C104KA55D"))
      (libsource (lib "eagle-import") (part "C_0402"))
    )
    (comp (ref "C134")
      (value "33pF")
      (footprint "eagle-import:C0402")
      (fields (field (name "MPN") "GCM1555C1H330FA16D"))
      (libsource (lib "eagle-import") (part "C_0402"))
    )
    (comp (ref "C135")
      (value "3pF")
      (footprint "eagle-import:C0402")
      (fields (field (name "MPN") "GCM1555C1H3R0BA16D"))
      (libsource (lib "eagle-import") (part "C_0402"))
    )
    (comp (ref "C136")
      (value "0.1uF")
      (footprint "eagle-import:C0402")
      (fields (field (name "MPN") "GCM155R71C104KA55D"))
      (libsource (lib "eagle-import") (part "C_0402"))
    )
    (comp (ref "C137")
      (value "0.1uF")
      (footprint "eagle-import:C0402")
      (fields (field (name "MPN") "GCM155R71C104KA55D"))
      (libsource (lib "eagle-import") (part "C_0402"))
    )
    (comp (ref "D1")
      (value "SMAJ150A")
      (footprint "eagle-import:DO214AC-HV")
      (fields (field (name "MPN") "SMAJ150A"))
      (libsource (lib "eagle-import") (part "SMAJA-HVXXX"))
    )
    (comp (ref "D2")
      (value "BAS101S,215")
      (footprint "eagle-import:SOT23-ROUNDED")
      (fields (field (name "MPN") "BAS101S,215"))
      (libsource (lib "eagle-import") (part "MMBD3004S-ROUNDED"))
    )
    (comp (ref "D3")
      (value "BAS101S,215")
      (footprint "eagle-import:SOT23-ROUNDED")
      (fields (field (name "MPN") "BAS101S,215"))
      (libsource (lib "eagle-import") (part "MMBD3004S-ROUNDED"))
    )
    (comp (ref "D4")
      (value "BAS101S,215")
      (footprint "eagle-import:SOT23-ROUNDED")
      (fields (field (name "MPN") "BAS101S,215"))
      (libsource (lib "eagle-import") (part "MMBD3004S-ROUNDED"))
    )
    (comp (ref "D5")
      (value "BAS101S,215")
      (footprint "eagle-import:SOT23-ROUNDED")
      (fields (field (name "MPN") "BAS101S,215"))
      (libsource (lib "eagle-import") (part "MMBD3004S-ROUNDED"))
    )
    (comp (ref "D6")
      (value "BAS101S,215")
      (footprint "eagle-import:SOT23-ROUNDED")
      (fields (field (name "MPN") "BAS101S,215"))
      (libsource (lib "eagle-import") (part "MMBD3004S-ROUNDED"))
    )
    (comp (ref "D7")
      (value "BAS101S,215")
      (footprint "eagle-import:SOT23-ROUNDED")
      (fields (field (name "MPN") "BAS101S,215"))
      (libsource (lib "eagle-import") (part "MMBD3004S-ROUNDED"))
    )
    (comp (ref "D8")
      (value "BAS101S,215")
      (footprint "eagle-import:SOT23-ROUNDED")
      (fields (field (name "MPN") "BAS101S,215"))
      (libsource (lib "eagle-import") (part "MMBD3004S-ROUNDED"))
    )
    (comp (ref "D9")
      (value "BAS101S,215")
      (footprint "eagle-import:SOT23-ROUNDED")
      (fields (field (name "MPN") "BAS101S,215"))
      (libsource (lib "eagle-import") (part "MMBD3004S-ROUNDED"))
    )
    (comp (ref "D10")
      (value "BAS101S,215")
      (footprint "eagle-import:SOT23-ROUNDED")
      (fields (field (name "MPN") "BAS101S,215"))
      (libsource (lib "eagle-import") (part "MMBD3004S-ROUNDED"))
    )
    (comp (ref "D11")
      (value "BAS101S,215")
      (footprint "eagle-import:SOT23-ROUNDED")
      (fields (field (name "MPN") "BAS101S,215"))
      (libsource (lib "eagle-import") (part "MMBD3004S-ROUNDED"))
    )
    (comp (ref "D12")
      (value "BAS101S,215")
      (footprint "eagle-import:SOT23-ROUNDED")
      (fields (field (name "MPN") "BAS101S,215"))
      (libsource (lib "eagle-import") (part "MMBD3004S-ROUNDED"))
    )
    (comp (ref "D13")
      (value "BAS101S,215")
      (footprint "eagle-import:SOT23-ROUNDED")
      (fields (field (name "MPN") "BAS101S,215"))
      (libsource (lib "eagle-import") (part "MMBD3004S-ROUNDED"))
    )
    (comp (ref "D14")
      (value "BAS101S,215")
      (footprint "eagle-import:SOT23-ROUNDED")
      (fields (field (name "MPN") "BAS101S,215"))
      (libsource (lib "eagle-import") (part "MMBD3004S-ROUNDED"))
    )
    (comp (ref "D15")
      (value "BAV99W,115")
      (footprint "eagle-import:SC70-3L")
      (fields (field (name "MPN") "BAV99W,115"))
      (libsource (lib "eagle-import") (part "BAV99W"))
    )
    (comp (ref "D16")
      (value "BAV99W,115")
      (footprint "eagle-import:SC70-3L")
      (fields (field (name "MPN") "BAV99W,115"))
      (libsource (lib "eagle-import") (part "BAV99W"))
    )
    (comp (ref "DY1")
      (value "PAD-0430-BARE")
      (footprint "eagle-import:0430-BARE")
      (libsource (lib "eagle-import") (part "PAD-0430-BARE"))
    )
    (comp (ref "DY2")
      (value "PAD-0430-BARE")
      (footprint "eagle-import:0430-BARE")
      (libsource (lib "eagle-import") (part "PAD-0430-BARE"))
    )
    (comp (ref "DY3")
      (value "PAD-0430-BARE")
      (footprint "eagle-import:0430-BARE")
      (libsource (lib "eagle-import") (part "PAD-0430-BARE"))
    )
    (comp (ref "DY4")
      (value "PAD-0430-BARE")
      (footprint "eagle-import:0430-BARE")
      (libsource (lib "eagle-import") (part "PAD-0430-BARE"))
    )
    (comp (ref "DY5")
      (value "PAD-0430-BARE")
      (footprint "eagle-import:0430-BARE")
      (libsource (lib "eagle-import") (part "PAD-0430-BARE"))
    )
    (comp (ref "DY6")
      (value "PAD-0430-BARE")
      (footprint "eagle-import:0430-BARE")
      (libsource (lib "eagle-import") (part "PAD-0430-BARE"))
    )
    (comp (ref "DY7")
      (value "PAD-0430-BARE")
      (footprint "eagle-import:0430-BARE")
      (libsource (lib "eagle-import") (part "PAD-0430-BARE"))
    )
    (comp (ref "DY8")
      (value "PAD-0430-BARE")
      (footprint "eagle-import:0430-BARE")
      (libsource (lib "eagle-import") (part "PAD-0430-BARE"))
    )
    (comp (ref "DY9")
      (value "PAD-0430-BARE")
      (footprint "eagle-import:0430-BARE")
      (libsource (lib "eagle-import") (part "PAD-0430-BARE"))
    )
    (comp (ref "DY10")
      (value "PAD-0430-BARE")
      (footprint "eagle-import:0430-BARE")
      (libsource (lib "eagle-import") (part "PAD-0430-BARE"))
    )
    (comp (ref "FID1")
      (value "FIDUCIAL_0.5MM")
      (footprint "eagle-import:FIDUCIAL_0.5MM")
      (fields (field (name "HOUSEPART") "NO"))
      (libsource (lib "eagle-import") (part "FIDUCIAL_0.5MM"))
    )
    (comp (ref "FID2")
      (value "FIDUCIAL_0.5MM")
      (footprint "eagle-import:FIDUCIAL_0.5MM")
      (fields (field (name "HOUSEPART") "NO"))
      (libsource (lib "eagle-import") (part "FIDUCIAL_0.5MM"))
    )
    (comp (ref "IC1")
      (value "74LVC1T45DCK")
      (footprint "eagle-import:SC70-6L-TI")
      (fields (field (name "MPN") "74LVC1T45GW-Q100H"))
      (libsource (lib "eagle-import") (part "741T45DCKLVC"))
    )
    (comp (ref "IC2")
      (value "AD8014ART")
      (footprint "eagle-import:SOT23-5")
      (fields (field (name "MPN") "AD8014ARTZ-REEL7"))
      (libsource (lib "eagle-import") (part "AD8014ART"))
    )
    (comp (ref "IC3")
      (value "MAX9013EUA")
      (footprint "eagle-import:MSOP8")
      (fields (field (name "MPN") "MAX9013EUA+"))
      (libsource (lib "eagle-import") (part "MAX9013EUA"))
    )
    (comp (ref "IC4")
      (value "SN74AUC1G17DCK")
      (footprint "eagle-import:SC70-5L-TI")
      (fields (field (name "MPN") "SN74AUC1G17DCKR"))
      (libsource (lib "eagle-import") (part "SN741G17DCKAUC"))
    )
    (comp (ref "IC5")
      (value "AD8014ART")
      (footprint "eagle-import:SOT23-5")
      (fields (field (name "MPN") "AD8014ARTZ-REEL7"))
      (libsource (lib "eagle-import") (part "AD8014ART"))
    )
    (comp (ref "IC6")
      (value "THS4551IRGT")
      (footprint "eagle-import:LFCSP16")
      (fields (field (name "MPN") "THS4551IRGTR"))
      (libsource (lib "eagle-import") (part "ADA4940-1ACPZ"))
    )
    (comp (ref "IC7")
      (value "THS4551IRGT")
      (footprint "eagle-import:LFCSP16")
      (fields (field (name "MPN") "THS4551IRGTR"))
      (libsource (lib "eagle-import") (part "ADA4940-1ACPZ"))
    )
    (comp (ref "IC8")
      (value "STM32L552CCU")
      (footprint "eagle-import:UFQFPN48-STMICRO")
      (fields (field (name "MPN") "STM32L552CCU6"))
      (libsource (lib "eagle-import") (part "STM32L552CUC"))
    )
    (comp (ref "IC9")
      (value "ICE40UP5K-SG48I")
      (footprint "eagle-import:QFN48-ICE40ULTRA")
      (fields (field (name "MPN") "ICE40UP5K-SG48I"))
      (libsource (lib "eagle-import") (part "ICE40UP5K-SG48I"))
    )
    (comp (ref "IC10")
      (value "LTC2142IUP-12")
      (footprint "eagle-import:QFN64-LTC214X")
      (fields (field (name "MPN") "LTC2141IUP-12"))
      (libsource (lib "eagle-import") (part "LTC2141-12UP"))
    )
    (comp (ref "IC11")
      (value "74AUP2G3404GW")
      (footprint "eagle-import:SC70-6L-TI")
      (fields (field (name "MPN") "74AUP2G3404GW,125"))
      (libsource (lib "eagle-import") (part "742G3404GWAUP"))
    )
    (comp (ref "IC12")
      (value "INA199C2DCK")
      (footprint "eagle-import:SC70-6L-TI")
      (fields (field (name "MPN") "INA199C2DCKR"))
      (libsource (lib "eagle-import") (part "INA199DCKB2"))
    )
    (comp (ref "IC13")
      (value "74AUP2G3404GW")
      (footprint "eagle-import:SC70-6L-TI")
      (fields (field (name "MPN") "74AUP2G3404GW,125"))
      (libsource (lib "eagle-import") (part "742G3404GWAUP"))
    )
    (comp (ref "J1")
      (value "HDR-16")
      (footprint "eagle-import:3M-45216-220230")
      (fields
        (field (name "MPN") "45216-220230")
        (field (name "MFG") "3M")
        (field (name "MPN_1") "45216-220230")
      )
      (libsource (lib "eagle-import") (part "HDR-2X8-3M-45216-220230"))
    )
    (comp (ref "J2")
      (value "COAX-2GNDU.FL")
      (footprint "eagle-import:HIROSE_U.FL-R-SMT-1")
      (fields (field (name "MPN") "U.FL-R-SMT-1(10)"))
      (libsource (lib "eagle-import") (part "COAX-2GNDU.FL"))
    )
    (comp (ref "J3")
      (value "COAX-2GNDU.FL")
      (footprint "eagle-import:HIROSE_U.FL-R-SMT-1")
      (fields (field (name "MPN") "U.FL-R-SMT-1(10)"))
      (libsource (lib "eagle-import") (part "COAX-2GNDU.FL"))
    )
    (comp (ref "J4")
      (value "HDR-2-SMD")
      (footprint "eagle-import:HEADER-SMD-2X1-MINIMUM")
      (fields
        (field (name "POPULATE") "1")
        (field (name "MFG") "Molex")
        (field (name "MPN") "87898")
        (field (name "POPULATE_1") "0")
      )
      (libsource (lib "eagle-import") (part "HDR-2-SMD"))
    )
    (comp (ref "K")
      (value "PAD-0430-BARE")
      (footprint "eagle-import:0430-BARE")
      (libsource (lib "eagle-import") (part "PAD-0430-BARE"))
    )
    (comp (ref "L1")
      (value "MMZ1005S601HTD25")
      (footprint "eagle-import:L0402")
      (fields (field (name "MPN") "MMZ1005S601ETD25"))
      (libsource (lib "eagle-import") (part "L_0402"))
    )
    (comp (ref "L2")
      (value "MMZ1005A222ETD25")
      (footprint "eagle-import:L0402-HV")
      (fields (field (name "MPN") "MMZ1005A222ETD25"))
      (libsource (lib "eagle-import") (part "L_0402HV"))
    )
    (comp (ref "L3")
      (value "1000uH/LPS4040")
      (footprint "eagle-import:LPS4040-REDUCED")
      (fields (field (name "MPN") "LPS4040-105MRC"))
      (libsource (lib "eagle-import") (part "L_LPS4040-REDUCED"))
    )
    (comp (ref "L4")
      (value "MMZ1005A222ETD25")
      (footprint "eagle-import:L0402-HV")
      (fields (field (name "MPN") "MMZ1005A222ETD25"))
      (libsource (lib "eagle-import") (part "L_0402HV"))
    )
    (comp (ref "L5")
      (value "10000uH/LPS6235")
      (footprint "eagle-import:LPS6235-REDUCED")
      (fields (field (name "MPN") "LPS6235-106MRC"))
      (libsource (lib "eagle-import") (part "L_LPS6235-REDUCED"))
    )
    (comp (ref "L6")
      (value "MMZ1005A222ETD25")
      (footprint "eagle-import:L0402-HV")
      (fields (field (name "MPN") "MMZ1005A222ETD25"))
      (libsource (lib "eagle-import") (part "L_0402HV"))
    )
    (comp (ref "L7")
      (value "MMZ1005S601HTD25")
      (footprint "eagle-import:L0402")
      (fields (field (name "MPN") "MMZ1005S601ETD25"))
      (libsource (lib "eagle-import") (part "L_0402"))
    )
    (comp (ref "L8")
      (value "MMZ1005S601HTD25")
      (footprint "eagle-import:L0402")
      (fields (field (name "MPN") "MMZ1005S601ETD25"))
      (libsource (lib "eagle-import") (part "L_0402"))
    )
    (comp (ref "L9")
      (value "MMZ1005A222ETD25")
      (footprint "eagle-import:L0402")
      (fields (field (name "MPN") "MMZ1005A222ETD25"))
      (libsource (lib "eagle-import") (part "L_0402"))
    )
    (comp (ref "L10")
      (value "MMZ1005A222ETD25")
      (footprint "eagle-import:L0402")
      (fields (field (name "MPN") "MMZ1005A222ETD25"))
      (libsource (lib "eagle-import") (part "L_0402"))
    )
    (comp (ref "L11")
      (value "MMZ1005S601HTD25")
      (footprint "eagle-import:L0402")
      (fields (field (name "MPN") "MMZ1005S601ETD25"))
      (libsource (lib "eagle-import") (part "L_0402"))
    )
    (comp (ref "L12")
      (value "MMZ1005A222ETD25")
      (footprint "eagle-import:L0402")
      (fields (field (name "MPN") "MMZ1005A222ETD25"))
      (libsource (lib "eagle-import") (part "L_0402"))
    )
    (comp (ref "L13")
      (value "MLZ2012N101LT")
      (footprint "eagle-import:L0805")
      (fields (field (name "MPN") "MLZ2012N101LTD25"))
      (libsource (lib "eagle-import") (part "L_0805"))
    )
    (comp (ref "L14")
      (value "MMZ1005A222ETD25")
      (footprint "eagle-import:L0402")
      (fields (field (name "MPN") "MMZ1005A222ETD25"))
      (libsource (lib "eagle-import") (part "L_0402"))
    )
    (comp (ref "L15")
      (value "MMZ1005S601HTD25")
      (footprint "eagle-import:L0402")
      (fields (field (name "MPN") "MMZ1005S601ETD25"))
      (libsource (lib "eagle-import") (part "L_0402"))
    )
    (comp (ref "L16")
      (value "MMZ1005A222ETD25")
      (footprint "eagle-import:L0402")
      (fields (field (name "MPN") "MMZ1005A222ETD25"))
      (libsource (lib "eagle-import") (part "L_0402"))
    )
    (comp (ref "L17")
      (value "MMZ1005A222ETD25")
      (footprint "eagle-import:L0402")
      (fields (field (name "MPN") "MMZ1005A222ETD25"))
      (libsource (lib "eagle-import") (part "L_0402"))
    )
    (comp (ref "L18")
      (value "MMZ1005S601HTD25")
      (footprint "eagle-import:L0402")
      (fields (field (name "MPN") "MMZ1005S601ETD25"))
      (libsource (lib "eagle-import") (part "L_0402"))
    )
    (comp (ref "L19")
      (value "MMZ1005S601HTD25")
      (footprint "eagle-import:L0402")
      (fields (field (name "MPN") "MMZ1005S601ETD25"))
      (libsource (lib "eagle-import") (part "L_0402"))
    )
    (comp (ref "R1")
      (value "1")
      (footprint "eagle-import:R0402")
      (fields (field (name "MPN") "AC0402FR-071RL"))
      (libsource (lib "eagle-import") (part "R_0402"))
    )
    (comp (ref "R2")
      (value "1M/150V")
      (footprint "eagle-import:R0805-HV")
      (fields (field (name "MPN") "AC0805FR-071ML"))
      (libsource (lib "eagle-import") (part "R_0805HV"))
    )
    (comp (ref "R3")
      (value "390K")
      (footprint "eagle-import:R0402-HV")
      (fields (field (name "MPN") "AC0402FR-07390KL"))
      (libsource (lib "eagle-import") (part "R_0402HV"))
    )
    (comp (ref "R4")
      (value "200M/200V")
      (footprint "eagle-import:R1206-HV")
      (fields (field (name "MPN") "CRCW1206200MJPEAHR"))
      (libsource (lib "eagle-import") (part "R_1206HV"))
    )
    (comp (ref "R5")
      (value "200M/200V")
      (footprint "eagle-import:R1206-HV")
      (fields (field (name "MPN") "CRCW1206200MJPEAHR"))
      (libsource (lib "eagle-import") (part "R_1206HV"))
    )
    (comp (ref "R6")
      (value "200M/200V")
      (footprint "eagle-import:R1206-HV")
      (fields (field (name "MPN") "CRCW1206200MJPEAHR"))
      (libsource (lib "eagle-import") (part "R_1206HV"))
    )
    (comp (ref "R7")
      (value "200M/200V")
      (footprint "eagle-import:R1206-HV")
      (fields (field (name "MPN") "CRCW1206200MJPEAHR"))
      (libsource (lib "eagle-import") (part "R_1206HV"))
    )
    (comp (ref "R8")
      (value "200M/200V")
      (footprint "eagle-import:R1206-HV")
      (fields (field (name "MPN") "CRCW1206200MJPEAHR"))
      (libsource (lib "eagle-import") (part "R_1206HV"))
    )
    (comp (ref "R9")
      (value "200M/200V")
      (footprint "eagle-import:R1206-HV")
      (fields (field (name "MPN") "CRCW1206200MJPEAHR"))
      (libsource (lib "eagle-import") (part "R_1206HV"))
    )
    (comp (ref "R10")
      (value "200M/200V")
      (footprint "eagle-import:R1206-HV")
      (fields (field (name "MPN") "CRCW1206200MJPEAHR"))
      (libsource (lib "eagle-import") (part "R_1206HV"))
    )
    (comp (ref "R11")
      (value "200M/200V")
      (footprint "eagle-import:R1206-HV")
      (fields (field (name "MPN") "CRCW1206200MJPEAHR"))
      (libsource (lib "eagle-import") (part "R_1206HV"))
    )
    (comp (ref "R12")
      (value "200M/200V")
      (footprint "eagle-import:R1206-HV")
      (fields (field (name "MPN") "CRCW1206200MJPEAHR"))
      (libsource (lib "eagle-import") (part "R_1206HV"))
    )
    (comp (ref "R13")
      (value "200M/200V")
      (footprint "eagle-import:R1206-HV")
      (fields (field (name "MPN") "CRCW1206200MJPEAHR"))
      (libsource (lib "eagle-import") (part "R_1206HV"))
    )
    (comp (ref "R14")
      (value "200M/200V")
      (footprint "eagle-import:R1206-HV")
      (fields (field (name "MPN") "CRCW1206200MJPEAHR"))
      (libsource (lib "eagle-import") (part "R_1206HV"))
    )
    (comp (ref "R15")
      (value "200M/200V")
      (footprint "eagle-import:R1206-HV")
      (fields (field (name "MPN") "CRCW1206200MJPEAHR"))
      (libsource (lib "eagle-import") (part "R_1206HV"))
    )
    (comp (ref "R16")
      (value "1.1M")
      (footprint "eagle-import:R0402")
      (fields (field (name "MPN") "AC0402FR-071M1L"))
      (libsource (lib "eagle-import") (part "R_0402"))
    )
    (comp (ref "R17")
      (value "390K")
      (footprint "eagle-import:R0402-HV")
      (fields (field (name "MPN") "AC0402FR-07390KL"))
      (libsource (lib "eagle-import") (part "R_0402HV"))
    )
    (comp (ref "R18")
      (value "390K")
      (footprint "eagle-import:R0402-HV")
      (fields (field (name "MPN") "AC0402FR-07390KL"))
      (libsource (lib "eagle-import") (part "R_0402HV"))
    )
    (comp (ref "R19")
      (value "390K")
      (footprint "eagle-import:R0402-HV")
      (fields (field (name "MPN") "AC0402FR-07390KL"))
      (libsource (lib "eagle-import") (part "R_0402HV"))
    )
    (comp (ref "R20")
      (value "390K")
      (footprint "eagle-import:R0402-HV")
      (fields (field (name "MPN") "AC0402FR-07390KL"))
      (libsource (lib "eagle-import") (part "R_0402HV"))
    )
    (comp (ref "R21")
      (value "390K")
      (footprint "eagle-import:R0402-HV")
      (fields (field (name "MPN") "AC0402FR-07390KL"))
      (libsource (lib "eagle-import") (part "R_0402HV"))
    )
    (comp (ref "R22")
      (value "390K")
      (footprint "eagle-import:R0402-HV")
      (fields (field (name "MPN") "AC0402FR-07390KL"))
      (libsource (lib "eagle-import") (part "R_0402HV"))
    )
    (comp (ref "R23")
      (value "390K")
      (footprint "eagle-import:R0402-HV")
      (fields (field (name "MPN") "AC0402FR-07390KL"))
      (libsource (lib "eagle-import") (part "R_0402HV"))
    )
    (comp (ref "R24")
      (value "390K")
      (footprint "eagle-import:R0402-HV")
      (fields (field (name "MPN") "AC0402FR-07390KL"))
      (libsource (lib "eagle-import") (part "R_0402HV"))
    )
    (comp (ref "R25")
      (value "390K")
      (footprint "eagle-import:R0402-HV")
      (fields (field (name "MPN") "AC0402FR-07390KL"))
      (libsource (lib "eagle-import") (part "R_0402HV"))
    )
    (comp (ref "R26")
      (value "390K")
      (footprint "eagle-import:R0402-HV")
      (fields (field (name "MPN") "AC0402FR-07390KL"))
      (libsource (lib "eagle-import") (part "R_0402HV"))
    )
    (comp (ref "R27")
      (value "390K")
      (footprint "eagle-import:R0402-HV")
      (fields (field (name "MPN") "AC0402FR-07390KL"))
      (libsource (lib "eagle-import") (part "R_0402HV"))
    )
    (comp (ref "R28")
      (value "390K")
      (footprint "eagle-import:R0402-HV")
      (fields (field (name "MPN") "AC0402FR-07390KL"))
      (libsource (lib "eagle-import") (part "R_0402HV"))
    )
    (comp (ref "R29")
      (value "390K")
      (footprint "eagle-import:R0402-HV")
      (fields (field (name "MPN") "AC0402FR-07390KL"))
      (libsource (lib "eagle-import") (part "R_0402HV"))
    )
    (comp (ref "R30")
      (value "10M")
      (footprint "eagle-import:R0402")
      (fields (field (name "MPN") "AC0402FR-0710ML"))
      (libsource (lib "eagle-import") (part "R_0402"))
    )
    (comp (ref "R31")
      (value "47M/150V")
      (footprint "eagle-import:R0805-HV")
      (fields (field (name "MPN") "RC0805JR-0747ML"))
      (libsource (lib "eagle-import") (part "R_0805HV"))
    )
    (comp (ref "R32")
      (value "47M/150V")
      (footprint "eagle-import:R0805-HV")
      (fields (field (name "MPN") "RC0805JR-0747ML"))
      (libsource (lib "eagle-import") (part "R_0805HV"))
    )
    (comp (ref "R33")
      (value "27")
      (footprint "eagle-import:R0402")
      (fields (field (name "MPN") "AC0402FR-0727RL"))
      (libsource (lib "eagle-import") (part "R_0402"))
    )
    (comp (ref "R34")
      (value "27")
      (footprint "eagle-import:R0402")
      (fields (field (name "MPN") "AC0402FR-0727RL"))
      (libsource (lib "eagle-import") (part "R_0402"))
    )
    (comp (ref "R35")
      (value "1.1M")
      (footprint "eagle-import:R0402")
      (fields (field (name "MPN") "AC0402FR-071M1L"))
      (libsource (lib "eagle-import") (part "R_0402"))
    )
    (comp (ref "R36")
      (value "10M")
      (footprint "eagle-import:R0402")
      (fields (field (name "MPN") "AC0402FR-0710ML"))
      (libsource (lib "eagle-import") (part "R_0402"))
    )
    (comp (ref "R37")
      (value "47M/150V")
      (footprint "eagle-import:R0805-HV")
      (fields (field (name "MPN") "RC0805JR-0747ML"))
      (libsource (lib "eagle-import") (part "R_0805HV"))
    )
    (comp (ref "R38")
      (value "47M/150V")
      (footprint "eagle-import:R0805-HV")
      (fields (field (name "MPN") "RC0805JR-0747ML"))
      (libsource (lib "eagle-import") (part "R_0805HV"))
    )
    (comp (ref "R39")
      (value "390K")
      (footprint "eagle-import:R0402-HV")
      (fields (field (name "MPN") "AC0402FR-07390KL"))
      (libsource (lib "eagle-import") (part "R_0402HV"))
    )
    (comp (ref "R40")
      (value "390K")
      (footprint "eagle-import:R0402-HV")
      (fields (field (name "MPN") "AC0402FR-07390KL"))
      (libsource (lib "eagle-import") (part "R_0402HV"))
    )
    (comp (ref "R41")
      (value "390K")
      (footprint "eagle-import:R0402-HV")
      (fields (field (name "MPN") "AC0402FR-07390KL"))
      (libsource (lib "eagle-import") (part "R_0402HV"))
    )
    (comp (ref "R42")
      (value "1K")
      (footprint "eagle-import:R0402")
      (fields (field (name "MPN") "AC0402FR-071KL"))
      (libsource (lib "eagle-import") (part "R_0402"))
    )
    (comp (ref "R45")
      (value "49.9")
      (footprint "eagle-import:R0402-HV")
      (fields (field (name "MPN") "AC0402FR-0749R9L"))
      (libsource (lib "eagle-import") (part "R_0402HV"))
    )
    (comp (ref "R46")
      (value "49.9")
      (footprint "eagle-import:R0402-HV")
      (fields (field (name "MPN") "AC0402FR-0749R9L"))
      (libsource (lib "eagle-import") (part "R_0402HV"))
    )
    (comp (ref "R47")
      (value "100K")
      (footprint "eagle-import:R0402-HV")
      (fields (field (name "MPN") "AC0402FR-07100KL"))
      (libsource (lib "eagle-import") (part "R_0402HV"))
    )
    (comp (ref "R48")
      (value "49.9")
      (footprint "eagle-import:R0402-HV")
      (fields (field (name "MPN") "AC0402FR-0749R9L"))
      (libsource (lib "eagle-import") (part "R_0402HV"))
    )
    (comp (ref "R49")
      (value "1K")
      (footprint "eagle-import:R0402")
      (fields (field (name "MPN") "AC0402FR-071KL"))
      (libsource (lib "eagle-import") (part "R_0402"))
    )
    (comp (ref "R50")
      (value "510")
      (footprint "eagle-import:R0402")
      (fields (field (name "MPN") "AC0402FR-07510RL"))
      (libsource (lib "eagle-import") (part "R_0402"))
    )
    (comp (ref "R51")
      (value "47K")
      (footprint "eagle-import:R0402")
      (fields (field (name "MPN") "AC0402FR-0747KL"))
      (libsource (lib "eagle-import") (part "R_0402"))
    )
    (comp (ref "R52")
      (value "1.2K")
      (footprint "eagle-import:R0402")
      (fields (field (name "MPN") "AC0402FR-071K2L"))
      (libsource (lib "eagle-import") (part "R_0402"))
    )
    (comp (ref "R53")
      (value "22")
      (footprint "eagle-import:R0402")
      (fields (field (name "MPN") "AC0402FR-0722RL"))
      (libsource (lib "eagle-import") (part "R_0402"))
    )
    (comp (ref "R54")
      (value "270")
      (footprint "eagle-import:R0402")
      (fields (field (name "MPN") "AC0402FR-07270RL"))
      (libsource (lib "eagle-import") (part "R_0402"))
    )
    (comp (ref "R55")
      (value "200")
      (footprint "eagle-import:R0402")
      (fields (field (name "MPN") "AC0402FR-07200RL"))
      (libsource (lib "eagle-import") (part "R_0402"))
    )
    (comp (ref "R56")
      (value "1K")
      (footprint "eagle-import:R0402")
      (fields (field (name "MPN") "AC0402FR-071KL"))
      (libsource (lib "eagle-import") (part "R_0402"))
    )
    (comp (ref "R57")
      (value "1K")
      (footprint "eagle-import:R0402")
      (fields (field (name "MPN") "AC0402FR-071KL"))
      (libsource (lib "eagle-import") (part "R_0402"))
    )
    (comp (ref "R58")
      (value "DNL")
      (footprint "eagle-import:R0402")
      (fields (field (name "POPULATE") "1") (field (name "POPULATE_1") "0"))
      (libsource (lib "eagle-import") (part "R_0402"))
    )
    (comp (ref "R59")
      (value "200")
      (footprint "eagle-import:R0402")
      (fields (field (name "MPN") "AC0402FR-07200RL"))
      (libsource (lib "eagle-import") (part "R_0402"))
    )
    (comp (ref "R60")
      (value "56")
      (footprint "eagle-import:R0402")
      (fields (field (name "MPN") "AC0402FR-0756RL"))
      (libsource (lib "eagle-import") (part "R_0402"))
    )
    (comp (ref "R61")
      (value "DNL")
      (footprint "eagle-import:R0402")
      (fields (field (name "POPULATE") "0"))
      (libsource (lib "eagle-import") (part "R_0402"))
    )
    (comp (ref "R62")
      (value "270K")
      (footprint "eagle-import:R0402")
      (fields (field (name "MPN") "AC0402FR-07270KL"))
      (libsource (lib "eagle-import") (part "R_0402"))
    )
    (comp (ref "R63")
      (value "DNL")
      (footprint "eagle-import:R0402")
      (fields (field (name "POPULATE") "0"))
      (libsource (lib "eagle-import") (part "R_0402"))
    )
    (comp (ref "R64")
      (value "20K")
      (footprint "eagle-import:R0402")
      (fields (field (name "MPN") "AC0402FR-0720KL"))
      (libsource (lib "eagle-import") (part "R_0402"))
    )
    (comp (ref "R65")
      (value "1K")
      (footprint "eagle-import:R0402")
      (fields (field (name "MPN") "AC0402FR-071KL"))
      (libsource (lib "eagle-import") (part "R_0402"))
    )
    (comp (ref "R67")
      (value "1.8K")
      (footprint "eagle-import:R0402")
      (fields (field (name "MPN") "AC0402FR-071K8L"))
      (libsource (lib "eagle-import") (part "R_0402"))
    )
    (comp (ref "R68")
      (value "750")
      (footprint "eagle-import:R0402")
      (fields (field (name "MPN") "AC0402FR-07750RL"))
      (libsource (lib "eagle-import") (part "R_0402"))
    )
    (comp (ref "R69")
      (value "330")
      (footprint "eagle-import:R0402")
      (fields (field (name "MPN") "AC0402FR-07330RL"))
      (libsource (lib "eagle-import") (part "R_0402"))
    )
    (comp (ref "R70")
      (value "220")
      (footprint "eagle-import:R0402")
      (fields (field (name "MPN") "AC0402FR-07220RL"))
      (libsource (lib "eagle-import") (part "R_0402"))
    )
    (comp (ref "R71")
      (value "1.8K")
      (footprint "eagle-import:R0402")
      (fields (field (name "MPN") "AC0402FR-071K8L"))
      (libsource (lib "eagle-import") (part "R_0402"))
    )
    (comp (ref "R72")
      (value "2.7K")
      (footprint "eagle-import:R0402")
      (fields (field (name "MPN") "AC0402FR-072K7L"))
      (libsource (lib "eagle-import") (part "R_0402"))
    )
    (comp (ref "R73")
      (value "330")
      (footprint "eagle-import:R0402")
      (fields (field (name "MPN") "AC0402FR-07330RL"))
      (libsource (lib "eagle-import") (part "R_0402"))
    )
    (comp (ref "R74")
      (value "220")
      (footprint "eagle-import:R0402")
      (fields (field (name "MPN") "AC0402FR-07220RL"))
      (libsource (lib "eagle-import") (part "R_0402"))
    )
    (comp (ref "R75")
      (value "430")
      (footprint "eagle-import:R0402")
      (fields (field (name "MPN") "AC0402FR-07430RL"))
      (libsource (lib "eagle-import") (part "R_0402"))
    )
    (comp (ref "R76")
      (value "1K")
      (footprint "eagle-import:R0402")
      (fields (field (name "MPN") "AC0402FR-071KL"))
      (libsource (lib "eagle-import") (part "R_0402"))
    )
    (comp (ref "R77")
      (value "1.2K")
      (footprint "eagle-import:R0402")
      (fields (field (name "MPN") "AC0402FR-071K2L"))
      (libsource (lib "eagle-import") (part "R_0402"))
    )
    (comp (ref "R78")
      (value "240")
      (footprint "eagle-import:R0402")
      (fields (field (name "MPN") "AC0402FR-07240RL"))
      (libsource (lib "eagle-import") (part "R_0402"))
    )
    (comp (ref "R79")
      (value "220")
      (footprint "eagle-import:R0402")
      (fields (field (name "MPN") "AC0402FR-07220RL"))
      (libsource (lib "eagle-import") (part "R_0402"))
    )
    (comp (ref "R80")
      (value "2.2K")
      (footprint "eagle-import:R0402")
      (fields (field (name "MPN") "AC0402FR-072K2L"))
      (libsource (lib "eagle-import") (part "R_0402"))
    )
    (comp (ref "R81")
      (value "1.8K")
      (footprint "eagle-import:R0402")
      (fields (field (name "MPN") "AC0402FR-071K8L"))
      (libsource (lib "eagle-import") (part "R_0402"))
    )
    (comp (ref "R83")
      (value "2.4K")
      (footprint "eagle-import:R0402")
      (fields (field (name "MPN") "AC0402FR-072K4L"))
      (libsource (lib "eagle-import") (part "R_0402"))
    )
    (comp (ref "R84")
      (value "240")
      (footprint "eagle-import:R0402")
      (fields (field (name "MPN") "AC0402FR-07240RL"))
      (libsource (lib "eagle-import") (part "R_0402"))
    )
    (comp (ref "R85")
      (value "220")
      (footprint "eagle-import:R0402")
      (fields (field (name "MPN") "AC0402FR-07220RL"))
      (libsource (lib "eagle-import") (part "R_0402"))
    )
    (comp (ref "R86")
      (value "1.8K")
      (footprint "eagle-import:R0402")
      (fields (field (name "MPN") "AC0402FR-071K8L"))
      (libsource (lib "eagle-import") (part "R_0402"))
    )
    (comp (ref "R87")
      (value "2.4K")
      (footprint "eagle-import:R0402")
      (fields (field (name "MPN") "AC0402FR-072K4L"))
      (libsource (lib "eagle-import") (part "R_0402"))
    )
    (comp (ref "R89")
      (value "2.2K")
      (footprint "eagle-import:R0402")
      (fields (field (name "MPN") "AC0402FR-072K2L"))
      (libsource (lib "eagle-import") (part "R_0402"))
    )
    (comp (ref "R90")
      (value "1K")
      (footprint "eagle-import:R0402")
      (fields (field (name "MPN") "AC0402FR-071KL"))
      (libsource (lib "eagle-import") (part "R_0402"))
    )
    (comp (ref "R91")
      (value "100")
      (footprint "eagle-import:R0402")
      (fields (field (name "MPN") "AC0402FR-07100RL"))
      (libsource (lib "eagle-import") (part "R_0402"))
    )
    (comp (ref "R92")
      (value "1K")
      (footprint "eagle-import:R0402")
      (fields (field (name "MPN") "AC0402FR-071KL"))
      (libsource (lib "eagle-import") (part "R_0402"))
    )
    (comp (ref "R93")
      (value "20K")
      (footprint "eagle-import:R0402")
      (fields (field (name "MPN") "AC0402FR-0720KL"))
      (libsource (lib "eagle-import") (part "R_0402"))
    )
    (comp (ref "R94")
      (value "100")
      (footprint "eagle-import:R0402")
      (fields (field (name "MPN") "AC0402FR-07100RL"))
      (libsource (lib "eagle-import") (part "R_0402"))
    )
    (comp (ref "R95")
      (value "10K")
      (footprint "eagle-import:R0402")
      (fields (field (name "MPN") "AC0402FR-0710KL"))
      (libsource (lib "eagle-import") (part "R_0402"))
    )
    (comp (ref "R98")
      (value "27")
      (footprint "eagle-import:R0402")
      (fields (field (name "MPN") "AC0402FR-0727RL"))
      (libsource (lib "eagle-import") (part "R_0402"))
    )
    (comp (ref "R99")
      (value "27")
      (footprint "eagle-import:R0402")
      (fields (field (name "MPN") "AC0402FR-0727RL"))
      (libsource (lib "eagle-import") (part "R_0402"))
    )
    (comp (ref "R101")
      (value "1")
      (footprint "eagle-import:R0402")
      (fields (field (name "MPN") "AC0402FR-071RL"))
      (libsource (lib "eagle-import") (part "R_0402"))
    )
    (comp (ref "R104")
      (value "100K")
      (footprint "eagle-import:R0402")
      (fields (field (name "MPN") "AC0402FR-07100KL"))
      (libsource (lib "eagle-import") (part "R_0402"))
    )
    (comp (ref "R108")
      (value "0")
      (footprint "eagle-import:R0402")
      (fields (field (name "MPN") "RC0402JR-070RL"))
      (libsource (lib "eagle-import") (part "R_0402"))
    )
    (comp (ref "R110")
      (value "100K")
      (footprint "eagle-import:R0402")
      (fields (field (name "MPN") "AC0402FR-07100KL"))
      (libsource (lib "eagle-import") (part "R_0402"))
    )
    (comp (ref "R111")
      (value "100K")
      (footprint "eagle-import:R0402")
      (fields (field (name "MPN") "AC0402FR-07100KL"))
      (libsource (lib "eagle-import") (part "R_0402"))
    )
  )
  (nets
    (net (code "1") (name "/(CDONE)") (class "Default")
      (node (ref "IC9") (pin "7") (pinfunction "CDONE_7") (pintype "bidirectional"))
    )
    (net (code "2") (name "/(FPGA_PIN11)") (class "Default")
      (node (ref "IC9") (pin "11") (pinfunction "IOB_20A_11") (pintype "bidirectional"))
    )
    (net (code "3") (name "/(SPI1_MISO_ALT)") (class "Default")
      (node (ref "IC8") (pin "40") (pinfunction "PB4_40") (pintype "bidirectional"))
    )
    (net (code "4") (name "/(SPI1_MOSI_ALT)") (class "Default")
      (node (ref "IC8") (pin "41") (pinfunction "PB5_41") (pintype "bidirectional"))
    )
    (net (code "5") (name "/+VAMP") (class "Default")
      (node (ref "C126") (pin "2") (pinfunction "2_2") (pintype "passive"))
      (node (ref "C61") (pin "1") (pinfunction "1_1") (pintype "passive"))
      (node (ref "C62") (pin "1") (pinfunction "1_1") (pintype "passive"))
      (node (ref "C86") (pin "1") (pinfunction "1_1") (pintype "passive"))
      (node (ref "C87") (pin "1") (pinfunction "1_1") (pintype "passive"))
      (node (ref "C89") (pin "1") (pinfunction "1_1") (pintype "passive"))
      (node (ref "C90") (pin "1") (pinfunction "1_1") (pintype "passive"))
      (node (ref "D15") (pin "2") (pinfunction "C2_2") (pintype "passive"))
      (node (ref "D16") (pin "2") (pinfunction "C2_2") (pintype "passive"))
      (node (ref "IC5") (pin "5") (pinfunction "V+_5") (pintype "power_in"))
      (node (ref "IC6") (pin "12") (pinfunction "~{DISABLE}_12") (pintype "bidirectional"))
      (node (ref "IC6") (pin "5") (pinfunction "+VS_5") (pintype "power_in"))
      (node (ref "IC6") (pin "6") (pinfunction "+VS_6") (pintype "power_in"))
      (node (ref "IC6") (pin "7") (pinfunction "+VS_7") (pintype "power_in"))
      (node (ref "IC6") (pin "8") (pinfunction "+VS_8") (pintype "power_in"))
      (node (ref "IC7") (pin "12") (pinfunction "~{DISABLE}_12") (pintype "bidirectional"))
      (node (ref "IC7") (pin "5") (pinfunction "+VS_5") (pintype "power_in"))
      (node (ref "IC7") (pin "6") (pinfunction "+VS_6") (pintype "power_in"))
      (node (ref "IC7") (pin "7") (pinfunction "+VS_7") (pintype "power_in"))
      (node (ref "IC7") (pin "8") (pinfunction "+VS_8") (pintype "power_in"))
      (node (ref "L17") (pin "2") (pinfunction "2_2") (pintype "passive"))
    )
    (net (code "6") (name "/+VAMP2") (class "Default")
      (node (ref "C125") (pin "2") (pinfunction "2_2") (pintype "passive"))
      (node (ref "C56") (pin "1") (pinfunction "1_1") (pintype "passive"))
      (node (ref "C57") (pin "1") (pinfunction "1_1") (pintype "passive"))
      (node (ref "IC2") (pin "5") (pinfunction "V+_5") (pintype "power_in"))
      (node (ref "L16") (pin "2") (pinfunction "2_2") (pintype "passive"))
      (node (ref "L7") (pin "2") (pinfunction "2_2") (pintype "passive"))
    )
    (net (code "7") (name "/+VDISC") (class "Default")
      (node (ref "C58") (pin "1") (pinfunction "1_1") (pintype "passive"))
      (node (ref "C59") (pin "1") (pinfunction "1_1") (pintype "passive"))
      (node (ref "IC3") (pin "1") (pinfunction "VCC_1") (pintype "power_in"))
      (node (ref "L7") (pin "1") (pinfunction "1_1") (pintype "passive"))
      (node (ref "R50") (pin "2") (pinfunction "2_2") (pintype "passive"))
    )
    (net (code "8") (name "/-DISCRIM_OUT_FPGA") (class "Default")
      (node (ref "IC9") (pin "2") (pinfunction "IOB_6A_2") (pintype "bidirectional"))
      (node (ref "R55") (pin "2") (pinfunction "2_2") (pintype "passive"))
    )
    (net (code "9") (name "/-DISCRIM_OUT_MCU") (class "Default")
      (node (ref "IC8") (pin "10") (pinfunction "PA0_10") (pintype "bidirectional"))
      (node (ref "R42") (pin "2") (pinfunction "2_2") (pintype "passive"))
    )
    (net (code "10") (name "/-VAMP") (class "Default")
      (node (ref "C120") (pin "2") (pinfunction "2_2") (pintype "passive"))
      (node (ref "C69") (pin "1") (pinfunction "1_1") (pintype "passive"))
      (node (ref "C70") (pin "1") (pinfunction "1_1") (pintype "passive"))
      (node (ref "D15") (pin "1") (pinfunction "A1_1") (pintype "passive"))
      (node (ref "IC5") (pin "2") (pinfunction "V-_2") (pintype "power_in"))
      (node (ref "L14") (pin "2") (pinfunction "2_2") (pintype "passive"))
      (node (ref "R49") (pin "1") (pinfunction "1_1") (pintype "passive"))
    )
    (net (code "11") (name "/-VAMP2") (class "Default")
      (node (ref "C117") (pin "2") (pinfunction "2_2") (pintype "passive"))
      (node (ref "C71") (pin "1") (pinfunction "1_1") (pintype "passive"))
      (node (ref "C72") (pin "1") (pinfunction "1_1") (pintype "passive"))
      (node (ref "IC2") (pin "2") (pinfunction "V-_2") (pintype "power_in"))
      (node (ref "L12") (pin "2") (pinfunction "2_2") (pintype "passive"))
      (node (ref "L8") (pin "2") (pinfunction "2_2") (pintype "passive"))
      (node (ref "R61") (pin "2") (pinfunction "2_2") (pintype "passive"))
    )
    (net (code "12") (name "/-VDISC") (class "Default")
      (node (ref "C66") (pin "1") (pinfunction "1_1") (pintype "passive"))
      (node (ref "C67") (pin "1") (pinfunction "1_1") (pintype "passive"))
      (node (ref "IC3") (pin "5") (pinfunction "LE_5") (pintype "input"))
      (node (ref "IC3") (pin "6") (pinfunction "GND_6") (pintype "power_in"))
      (node (ref "L8") (pin "1") (pinfunction "1_1") (pintype "passive"))
    )
    (net (code "13") (name "/ADC1_IN8") (class "Default")
      (node (ref "C50") (pin "1") (pinfunction "1_1") (pintype "passive"))
      (node (ref "IC8") (pin "13") (pinfunction "PA3_13") (pintype "bidirectional"))
      (node (ref "R35") (pin "2") (pinfunction "2_2") (pintype "passive"))
      (node (ref "R36") (pin "1") (pinfunction "1_1") (pintype "passive"))
    )
    (net (code "14") (name "/ADC1_IN12") (class "Default")
      (node (ref "C34") (pin "1") (pinfunction "1_1") (pintype "passive"))
      (node (ref "IC8") (pin "17") (pinfunction "PA7_17") (pintype "bidirectional"))
      (node (ref "R16") (pin "2") (pinfunction "2_2") (pintype "passive"))
      (node (ref "R30") (pin "1") (pinfunction "1_1") (pintype "passive"))
    )
    (net (code "15") (name "/ADC1_IN15") (class "Default")
      (node (ref "C131") (pin "2") (pinfunction "2_2") (pintype "passive"))
      (node (ref "IC8") (pin "18") (pinfunction "PB0_18") (pintype "bidirectional"))
      (node (ref "R111") (pin "1") (pinfunction "1_1") (pintype "passive"))
    )
    (net (code "16") (name "/ADC1_IN16") (class "Default")
      (node (ref "C129") (pin "2") (pinfunction "2_2") (pintype "passive"))
      (node (ref "IC12") (pin "1") (pinfunction "REF_1") (pintype "input"))
      (node (ref "IC8") (pin "19") (pinfunction "PB1_19") (pintype "bidirectional"))
      (node (ref "R110") (pin "1") (pinfunction "1_1") (pintype "passive"))
    )
    (net (code "17") (name "/ADC_CLKOUT") (class "Default")
      (node (ref "IC10") (pin "40") (pinfunction "CLKOUT+_40") (pintype "bidirectional"))
      (node (ref "IC9") (pin "20") (pinfunction "IOB_25B_G3_20") (pintype "bidirectional"))
    )
    (net (code "18") (name "/ADC_ENC") (class "Default")
      (node (ref "IC10") (pin "18") (pinfunction "ENC+_18") (pintype "bidirectional"))
      (node (ref "IC9") (pin "35") (pinfunction "IOT_46B_G0_35") (pintype "bidirectional"))
    )
    (net (code "19") (name "/ADC_OUT1_0") (class "Default")
      (node (ref "IC10") (pin "47") (pinfunction "D1_0_47") (pintype "bidirectional"))
      (node (ref "IC9") (pin "38") (pinfunction "IOT_50B_38") (pintype "bidirectional"))
    )
    (net (code "20") (name "/ADC_OUT1_1") (class "Default")
      (node (ref "IC10") (pin "48") (pinfunction "D1_1_48") (pintype "bidirectional"))
      (node (ref "IC9") (pin "37") (pinfunction "IOT_45A_G1_37") (pintype "bidirectional"))
    )
    (net (code "21") (name "/ADC_OUT1_2") (class "Default")
      (node (ref "IC10") (pin "49") (pinfunction "D1_2_49") (pintype "bidirectional"))
      (node (ref "IC9") (pin "36") (pinfunction "IOT_48B_36") (pintype "bidirectional"))
    )
    (net (code "22") (name "/ADC_OUT1_3") (class "Default")
      (node (ref "IC10") (pin "50") (pinfunction "D1_3_50") (pintype "bidirectional"))
      (node (ref "IC9") (pin "34") (pinfunction "IOT_44B_34") (pintype "bidirectional"))
    )
    (net (code "23") (name "/ADC_OUT1_4") (class "Default")
      (node (ref "IC10") (pin "51") (pinfunction "D1_4_51") (pintype "bidirectional"))
      (node (ref "IC9") (pin "32") (pinfunction "IOT_43A_32") (pintype "bidirectional"))
    )
    (net (code "24") (name "/ADC_OUT1_5") (class "Default")
      (node (ref "IC10") (pin "52") (pinfunction "D1_5_52") (pintype "bidirectional"))
      (node (ref "IC9") (pin "31") (pinfunction "IOT_42B_31") (pintype "bidirectional"))
    )
    (net (code "25") (name "/ADC_OUT1_6") (class "Default")
      (node (ref "IC10") (pin "53") (pinfunction "D1_6_53") (pintype "bidirectional"))
      (node (ref "IC9") (pin "28") (pinfunction "IOT_41A_28") (pintype "bidirectional"))
    )
    (net (code "26") (name "/ADC_OUT1_7") (class "Default")
      (node (ref "IC10") (pin "54") (pinfunction "D1_7_54") (pintype "bidirectional"))
      (node (ref "IC9") (pin "27") (pinfunction "IOT_38B_27") (pintype "bidirectional"))
    )
    (net (code "27") (name "/ADC_OUT1_8") (class "Default")
      (node (ref "IC10") (pin "55") (pinfunction "D1_8_55") (pintype "bidirectional"))
      (node (ref "IC9") (pin "26") (pinfunction "IOT_39A_26") (pintype "bidirectional"))
    )
    (net (code "28") (name "/ADC_OUT1_9") (class "Default")
      (node (ref "IC10") (pin "56") (pinfunction "D1_9_56") (pintype "bidirectional"))
      (node (ref "IC9") (pin "25") (pinfunction "IOT_36B_25") (pintype "bidirectional"))
    )
    (net (code "29") (name "/ADC_OUT1_10") (class "Default")
      (node (ref "IC10") (pin "57") (pinfunction "D1_10_57") (pintype "bidirectional"))
      (node (ref "IC9") (pin "23") (pinfunction "IOT_37A_23") (pintype "bidirectional"))
    )
    (net (code "30") (name "/ADC_OUT1_11") (class "Default")
      (node (ref "IC10") (pin "58") (pinfunction "D1_11_58") (pintype "bidirectional"))
      (node (ref "IC9") (pin "21") (pinfunction "IOB_23B_21") (pintype "bidirectional"))
    )
    (net (code "31") (name "/ADC_OUT2_0") (class "Default")
      (node (ref "IC10") (pin "27") (pinfunction "D2_0_27") (pintype "bidirectional"))
      (node (ref "IC9") (pin "10") (pinfunction "IOB_18A_10") (pintype "bidirectional"))
    )
    (net (code "32") (name "/ADC_OUT2_1") (class "Default")
      (node (ref "IC10") (pin "28") (pinfunction "D2_1_28") (pintype "bidirectional"))
      (node (ref "IC9") (pin "9") (pinfunction "IOB_16A_9") (pintype "bidirectional"))
    )
    (net (code "33") (name "/ADC_OUT2_2") (class "Default")
      (node (ref "IC10") (pin "29") (pinfunction "D2_2_29") (pintype "bidirectional"))
      (node (ref "IC9") (pin "6") (pinfunction "IOB_13B_6") (pintype "bidirectional"))
    )
    (net (code "34") (name "/ADC_OUT2_3") (class "Default")
      (node (ref "IC10") (pin "30") (pinfunction "D2_3_30") (pintype "bidirectional"))
      (node (ref "IC9") (pin "4") (pinfunction "IOB_8A_4") (pintype "bidirectional"))
    )
    (net (code "35") (name "/ADC_OUT2_4") (class "Default")
      (node (ref "IC10") (pin "31") (pinfunction "D2_4_31") (pintype "bidirectional"))
      (node (ref "IC9") (pin "3") (pinfunction "IOB_9B_3") (pintype "bidirectional"))
    )
    (net (code "36") (name "/ADC_OUT2_5") (class "Default")
      (node (ref "IC10") (pin "32") (pinfunction "D2_5_32") (pintype "bidirectional"))
      (node (ref "IC9") (pin "48") (pinfunction "IOB_4A_48") (pintype "bidirectional"))
    )
    (net (code "37") (name "/ADC_OUT2_6") (class "Default")
      (node (ref "IC10") (pin "33") (pinfunction "D2_6_33") (pintype "bidirectional"))
      (node (ref "IC9") (pin "47") (pinfunction "IOB_2A_47") (pintype "bidirectional"))
    )
    (net (code "38") (name "/ADC_OUT2_7") (class "Default")
      (node (ref "IC10") (pin "34") (pinfunction "D2_7_34") (pintype "bidirectional"))
      (node (ref "IC9") (pin "46") (pinfunction "IOB_0A_46") (pintype "bidirectional"))
    )
    (net (code "39") (name "/ADC_OUT2_8") (class "Default")
      (node (ref "IC10") (pin "35") (pinfunction "D2_8_35") (pintype "bidirectional"))
      (node (ref "IC9") (pin "45") (pinfunction "IOB_5B_45") (pintype "bidirectional"))
    )
    (net (code "40") (name "/ADC_OUT2_9") (class "Default")
      (node (ref "IC10") (pin "36") (pinfunction "D2_9_36") (pintype "bidirectional"))
      (node (ref "IC9") (pin "44") (pinfunction "IOT_3B_G6_44") (pintype "bidirectional"))
    )
    (net (code "41") (name "/ADC_OUT2_10") (class "Default")
      (node (ref "IC10") (pin "37") (pinfunction "D2_10_37") (pintype "bidirectional"))
      (node (ref "IC9") (pin "43") (pinfunction "IOT_49A_43") (pintype "bidirectional"))
    )
    (net (code "42") (name "/ADC_OUT2_11") (class "Default")
      (node (ref "IC10") (pin "38") (pinfunction "D2_11_38") (pintype "bidirectional"))
      (node (ref "IC9") (pin "42") (pinfunction "IOT_51A_42") (pintype "bidirectional"))
    )
    (net (code "43") (name "/ADC_~{CS}") (class "Default")
      (node (ref "IC10") (pin "20") (pinfunction "-CS_20") (pintype "bidirectional"))
      (node (ref "IC8") (pin "43") (pinfunction "PB7_43") (pintype "bidirectional"))
    )
    (net (code "44") (name "/AMP_VCM1") (class "Default")
      (node (ref "C92") (pin "1") (pinfunction "1_1") (pintype "passive"))
      (node (ref "IC10") (pin "2") (pinfunction "VCM1_2") (pintype "bidirectional"))
      (node (ref "IC6") (pin "9") (pinfunction "VOCM_9") (pintype "input"))
    )
    (net (code "45") (name "/AMP_VCM2") (class "Default")
      (node (ref "C102") (pin "1") (pinfunction "1_1") (pintype "passive"))
      (node (ref "IC10") (pin "15") (pinfunction "VCM2_15") (pintype "bidirectional"))
      (node (ref "IC7") (pin "9") (pinfunction "VOCM_9") (pintype "input"))
    )
    (net (code "46") (name "/ANODE") (class "Default")
      (node (ref "ANODE") (pin "P$1") (pinfunction "P_P$1") (pintype "passive"))
      (node (ref "C65") (pin "1") (pinfunction "1_1") (pintype "passive"))
      (node (ref "D15") (pin "3") (pinfunction "C1A2_3") (pintype "passive"))
      (node (ref "R51") (pin "2") (pinfunction "2_2") (pintype "passive"))
      (node (ref "R53") (pin "2") (pinfunction "2_2") (pintype "passive"))
    )
    (net (code "47") (name "/ANODE_AMP_OUTN") (class "Default")
      (node (ref "C82") (pin "1") (pinfunction "1_1") (pintype "passive"))
      (node (ref "IC10") (pin "5") (pinfunction "AIN1-_5") (pintype "bidirectional"))
      (node (ref "R79") (pin "2") (pinfunction "2_2") (pintype "passive"))
    )
    (net (code "48") (name "/ANODE_AMP_OUTP") (class "Default")
      (node (ref "C82") (pin "2") (pinfunction "2_2") (pintype "passive"))
      (node (ref "IC10") (pin "4") (pinfunction "AIN1+_4") (pintype "bidirectional"))
      (node (ref "R85") (pin "2") (pinfunction "2_2") (pintype "passive"))
    )
    (net (code "49") (name "/ANODE_PREAMP_OUT") (class "Default")
      (node (ref "C63") (pin "2") (pinfunction "2_2") (pintype "passive"))
      (node (ref "IC2") (pin "3") (pinfunction "IN+_3") (pintype "input"))
      (node (ref "IC5") (pin "1") (pinfunction "OUT_1") (pintype "output"))
      (node (ref "R52") (pin "1") (pinfunction "1_1") (pintype "passive"))
      (node (ref "R76") (pin "1") (pinfunction "1_1") (pintype "passive"))
      (node (ref "R77") (pin "1") (pinfunction "1_1") (pintype "passive"))
    )
    (net (code "50") (name "/BOOT_CONTROL") (class "Default")
      (node (ref "J4") (pin "2") (pinfunction "2_2") (pintype "passive"))
      (node (ref "R65") (pin "2") (pinfunction "2_2") (pintype "passive"))
    )
    (net (code "51") (name "/CLK20M_N") (class "Default")
      (node (ref "IC8") (pin "5") (pinfunction "PH0-OSC_IN_5") (pintype "bidirectional"))
      (node (ref "J1") (pin "3") (pinfunction "3_3") (pintype "passive"))
    )
    (net (code "52") (name "/CLK20M_P") (class "Default")
      (node (ref "IC9") (pin "18") (pinfunction "IOB_31B_18") (pintype "bidirectional"))
      (node (ref "J1") (pin "2") (pinfunction "2_2") (pintype "passive"))
    )
    (net (code "53") (name "/DISCRIM_IN+") (class "Default")
      (node (ref "C68") (pin "2") (pinfunction "2_2") (pintype "passive"))
      (node (ref "IC2") (pin "1") (pinfunction "OUT_1") (pintype "output"))
      (node (ref "IC3") (pin "2") (pinfunction "IN+_2") (pintype "input"))
      (node (ref "R56") (pin "2") (pinfunction "2_2") (pintype "passive"))
    )
    (net (code "54") (name "/DISCRIM_IN-") (class "Default")
      (node (ref "C73") (pin "1") (pinfunction "1_1") (pintype "passive"))
      (node (ref "C74") (pin "1") (pinfunction "1_1") (pintype "passive"))
      (node (ref "IC3") (pin "3") (pinfunction "IN-_3") (pintype "input"))
      (node (ref "R61") (pin "1") (pinfunction "1_1") (pintype "passive"))
      (node (ref "R62") (pin "1") (pinfunction "1_1") (pintype "passive"))
      (node (ref "R63") (pin "1") (pinfunction "1_1") (pintype "passive"))
    )
    (net (code "55") (name "/DISCRIM_LEVEL") (class "Default")
      (node (ref "IC8") (pin "14") (pinfunction "PA4_14") (pintype "bidirectional"))
      (node (ref "R62") (pin "2") (pinfunction "2_2") (pintype "passive"))
    )
    (net (code "56") (name "/DRV_OUT") (class "Default")
      (node (ref "C20") (pin "1") (pinfunction "1_1") (pintype "passive"))
      (node (ref "C5") (pin "1") (pinfunction "1_1") (pintype "passive"))
      (node (ref "L6") (pin "1") (pinfunction "1_1") (pintype "passive"))
    )
    (net (code "57") (name "/DY8_AMP_IN") (class "Default")
      (node (ref "C134") (pin "1") (pinfunction "1_1") (pintype "passive"))
      (node (ref "C135") (pin "1") (pinfunction "1_1") (pintype "passive"))
      (node (ref "C55") (pin "2") (pinfunction "2_2") (pintype "passive"))
      (node (ref "D16") (pin "3") (pinfunction "C1A2_3") (pintype "passive"))
      (node (ref "R58") (pin "2") (pinfunction "2_2") (pintype "passive"))
      (node (ref "R68") (pin "1") (pinfunction "1_1") (pintype "passive"))
      (node (ref "R75") (pin "2") (pinfunction "2_2") (pintype "passive"))
    )
    (net (code "58") (name "/DY9_AMP_OUTN") (class "Default")
      (node (ref "C77") (pin "1") (pinfunction "1_1") (pintype "passive"))
      (node (ref "IC10") (pin "12") (pinfunction "AIN2+_12") (pintype "bidirectional"))
      (node (ref "R70") (pin "2") (pinfunction "2_2") (pintype "passive"))
    )
    (net (code "59") (name "/DY9_AMP_OUTP") (class "Default")
      (node (ref "C77") (pin "2") (pinfunction "2_2") (pintype "passive"))
      (node (ref "IC10") (pin "13") (pinfunction "AIN2-_13") (pintype "bidirectional"))
      (node (ref "R74") (pin "2") (pinfunction "2_2") (pintype "passive"))
    )
    (net (code "60") (name "/FPGA_CRESET_B") (class "Default")
      (node (ref "IC8") (pin "21") (pinfunction "PB10_21") (pintype "bidirectional"))
      (node (ref "IC9") (pin "8") (pinfunction "CRESET_B_8") (pintype "bidirectional"))
    )
    (net (code "61") (name "/FPGA_C_~{CS}") (class "Default")
      (node (ref "IC8") (pin "25") (pinfunction "PB12_25") (pintype "bidirectional"))
      (node (ref "IC9") (pin "16") (pinfunction "IOB_35B_SPI_CSN_16") (pintype "bidirectional"))
      (node (ref "R95") (pin "1") (pinfunction "1_1") (pintype "passive"))
    )
    (net (code "62") (name "/FPGA_DRDY") (class "Default")
      (node (ref "IC8") (pin "29") (pinfunction "PA8_29") (pintype "bidirectional"))
      (node (ref "IC9") (pin "13") (pinfunction "IOB_24A_13") (pintype "bidirectional"))
    )
    (net (code "63") (name "/FPGA_RESTART") (class "Default")
      (node (ref "IC8") (pin "22") (pinfunction "PB11_22") (pintype "bidirectional"))
      (node (ref "IC9") (pin "12") (pinfunction "IOB_22A_12") (pintype "bidirectional"))
    )
    (net (code "64") (name "/SPI1_MISO") (class "Default")
      (node (ref "IC10") (pin "61") (pinfunction "SDO_61") (pintype "bidirectional"))
      (node (ref "IC8") (pin "32") (pinfunction "PA11_32") (pintype "bidirectional"))
      (node (ref "R89") (pin "2") (pinfunction "2_2") (pintype "passive"))
    )
    (net (code "65") (name "/SPI1_MOSI") (class "Default")
      (node (ref "IC10") (pin "22") (pinfunction "SDI_22") (pintype "bidirectional"))
      (node (ref "IC8") (pin "33") (pinfunction "PA12_33") (pintype "bidirectional"))
    )
    (net (code "66") (name "/SPI1_SCK") (class "Default")
      (node (ref "IC10") (pin "21") (pinfunction "SCK_21") (pintype "bidirectional"))
      (node (ref "IC8") (pin "39") (pinfunction "PB3_39") (pintype "bidirectional"))
    )
    (net (code "67") (name "/SPI2_MISO") (class "Default")
      (node (ref "IC8") (pin "27") (pinfunction "PB14_27") (pintype "bidirectional"))
      (node (ref "IC9") (pin "14") (pinfunction "IOB_32A_SPI_SO_14") (pintype "bidirectional"))
    )
    (net (code "68") (name "/SPI2_MOSI") (class "Default")
      (node (ref "IC8") (pin "28") (pinfunction "PB15_28") (pintype "bidirectional"))
      (node (ref "IC9") (pin "17") (pinfunction "IOB_33B_SPI_SI_17") (pintype "bidirectional"))
    )
    (net (code "69") (name "/SPI2_SCK") (class "Default")
      (node (ref "IC8") (pin "26") (pinfunction "PB13_26") (pintype "bidirectional"))
      (node (ref "IC9") (pin "15") (pinfunction "IOB_34A_SPI_SCK_15") (pintype "bidirectional"))
    )
    (net (code "70") (name "/SYNC") (class "Default")
      (node (ref "IC9") (pin "19") (pinfunction "IOB_29B_19") (pintype "bidirectional"))
      (node (ref "J1") (pin "8") (pinfunction "8_8") (pintype "passive"))
    )
    (net (code "71") (name "/TIM2_CH3_SOFT") (class "Default")
      (node (ref "IC1") (pin "3") (pinfunction "A_3") (pintype "bidirectional"))
      (node (ref "R92") (pin "1") (pinfunction "1_1") (pintype "passive"))
    )
    (net (code "72") (name "/TRIGOUT") (class "Default")
      (node (ref "IC13") (pin "1") (pinfunction "1A_1") (pintype "input"))
      (node (ref "IC13") (pin "3") (pinfunction "2A_3") (pintype "input"))
      (node (ref "IC8") (pin "15") (pinfunction "PA5_15") (pintype "bidirectional"))
    )
    (net (code "73") (name "/TRIGOUT_N") (class "Default")
      (node (ref "J1") (pin "5") (pinfunction "5_5") (pintype "passive"))
      (node (ref "R33") (pin "1") (pinfunction "1_1") (pintype "passive"))
    )
    (net (code "74") (name "/TRIGOUT_P") (class "Default")
      (node (ref "J1") (pin "6") (pinfunction "6_6") (pintype "passive"))
      (node (ref "R34") (pin "1") (pinfunction "1_1") (pintype "passive"))
    )
    (net (code "75") (name "/UART_RXD_N") (class "Default")
      (node (ref "J1") (pin "11") (pinfunction "11_11") (pintype "passive"))
    )
    (net (code "76") (name "/UART_RXD_P") (class "Default")
      (node (ref "J1") (pin "12") (pinfunction "12_12") (pintype "passive"))
      (node (ref "R90") (pin "1") (pinfunction "1_1") (pintype "passive"))
    )
    (net (code "77") (name "/UART_TXD_A") (class "Default")
      (node (ref "IC11") (pin "1") (pinfunction "1A_1") (pintype "input"))
      (node (ref "IC11") (pin "3") (pinfunction "2A_3") (pintype "input"))
      (node (ref "R91") (pin "1") (pinfunction "1_1") (pintype "passive"))
      (node (ref "R93") (pin "1") (pinfunction "1_1") (pintype "passive"))
    )
    (net (code "78") (name "/UART_TXD_N") (class "Default")
      (node (ref "J1") (pin "15") (pinfunction "15_15") (pintype "passive"))
      (node (ref "R99") (pin "1") (pinfunction "1_1") (pintype "passive"))
    )
    (net (code "79") (name "/UART_TXD_P") (class "Default")
      (node (ref "J1") (pin "14") (pinfunction "14_14") (pintype "passive"))
      (node (ref "R98") (pin "1") (pinfunction "1_1") (pintype "passive"))
    )
    (net (code "80") (name "/USART1_RX") (class "Default")
      (node (ref "IC8") (pin "31") (pinfunction "PA10_31") (pintype "bidirectional"))
      (node (ref "R90") (pin "2") (pinfunction "2_2") (pintype "passive"))
    )
    (net (code "81") (name "/USART1_TX") (class "Default")
      (node (ref "IC8") (pin "30") (pinfunction "PA9_30") (pintype "bidirectional"))
      (node (ref "R91") (pin "2") (pinfunction "2_2") (pintype "passive"))
    )
    (net (code "82") (name "/VDDA-ADC") (class "Default")
      (node (ref "C103") (pin "1") (pinfunction "1_1") (pintype "passive"))
      (node (ref "C128") (pin "2") (pinfunction "2_2") (pintype "passive"))
      (node (ref "C91") (pin "1") (pinfunction "1_1") (pintype "passive"))
      (node (ref "IC10") (pin "1") (pinfunction "VDD_1") (pintype "bidirectional"))
      (node (ref "IC10") (pin "16") (pinfunction "VDD_16") (pintype "bidirectional"))
      (node (ref "IC10") (pin "17") (pinfunction "VDD_17") (pintype "bidirectional"))
      (node (ref "IC10") (pin "63") (pinfunction "SENSE_63") (pintype "bidirectional"))
      (node (ref "IC10") (pin "64") (pinfunction "VDD_64") (pintype "bidirectional"))
      (node (ref "L18") (pin "2") (pinfunction "2_2") (pintype "passive"))
    )
    (net (code "83") (name "/VDDFPGA") (class "Default")
      (node (ref "C114") (pin "1") (pinfunction "1_1") (pintype "passive"))
      (node (ref "J1") (pin "7") (pinfunction "7_7") (pintype "passive"))
      (node (ref "L19") (pin "1") (pinfunction "1_1") (pintype "passive"))
    )
    (net (code "84") (name "/VDDFPGA-FILT") (class "Default")
      (node (ref "C100") (pin "1") (pinfunction "1_1") (pintype "passive"))
      (node (ref "C107") (pin "1") (pinfunction "1_1") (pintype "passive"))
      (node (ref "C130") (pin "1") (pinfunction "1_1") (pintype "passive"))
      (node (ref "IC9") (pin "30") (pinfunction "VCC_30") (pintype "bidirectional"))
      (node (ref "IC9") (pin "5") (pinfunction "VCC_5") (pintype "bidirectional"))
      (node (ref "L19") (pin "2") (pinfunction "2_2") (pintype "passive"))
      (node (ref "R94") (pin "1") (pinfunction "1_1") (pintype "passive"))
    )
    (net (code "85") (name "/VDDSW") (class "Default")
      (node (ref "C122") (pin "1") (pinfunction "1_1") (pintype "passive"))
      (node (ref "C132") (pin "2") (pinfunction "2_2") (pintype "passive"))
      (node (ref "IC12") (pin "3") (pinfunction "V+_3") (pintype "power_in"))
      (node (ref "IC12") (pin "4") (pinfunction "IN+_4") (pintype "bidirectional"))
      (node (ref "J1") (pin "10") (pinfunction "10_10") (pintype "passive"))
      (node (ref "R101") (pin "2") (pinfunction "2_2") (pintype "passive"))
    )
    (net (code "86") (name "/VDDSW-FILT") (class "Default")
      (node (ref "C119") (pin "1") (pinfunction "1_1") (pintype "passive"))
      (node (ref "L13") (pin "2") (pinfunction "2_2") (pintype "passive"))
      (node (ref "R1") (pin "1") (pinfunction "1_1") (pintype "passive"))
    )
    (net (code "87") (name "/VDDU") (class "Default")
      (node (ref "C127") (pin "1") (pinfunction "1_1") (pintype "passive"))
      (node (ref "J1") (pin "16") (pinfunction "16_16") (pintype "passive"))
      (node (ref "L11") (pin "1") (pinfunction "1_1") (pintype "passive"))
      (node (ref "L15") (pin "1") (pinfunction "1_1") (pintype "passive"))
      (node (ref "L18") (pin "1") (pinfunction "1_1") (pintype "passive"))
    )
    (net (code "88") (name "/VDDU-FILT") (class "Default")
      (node (ref "C104") (pin "1") (pinfunction "1_1") (pintype "passive"))
      (node (ref "C105") (pin "1") (pinfunction "1_1") (pintype "passive"))
      (node (ref "C106") (pin "1") (pinfunction "1_1") (pintype "passive"))
      (node (ref "C110") (pin "1") (pinfunction "1_1") (pintype "passive"))
      (node (ref "C118") (pin "1") (pinfunction "1_1") (pintype "passive"))
      (node (ref "C121") (pin "2") (pinfunction "2_2") (pintype "passive"))
      (node (ref "C133") (pin "1") (pinfunction "1_1") (pintype "passive"))
      (node (ref "C3") (pin "2") (pinfunction "2_2") (pintype "passive"))
      (node (ref "C64") (pin "2") (pinfunction "2_2") (pintype "passive"))
      (node (ref "C85") (pin "1") (pinfunction "1_1") (pintype "passive"))
      (node (ref "C88") (pin "1") (pinfunction "1_1") (pintype "passive"))
      (node (ref "C96") (pin "1") (pinfunction "1_1") (pintype "passive"))
      (node (ref "C99") (pin "1") (pinfunction "1_1") (pintype "passive"))
      (node (ref "IC1") (pin "1") (pinfunction "VCCA_1") (pintype "power_in"))
      (node (ref "IC1") (pin "5") (pinfunction "DIR_5") (pintype "input"))
      (node (ref "IC10") (pin "42") (pinfunction "OVDD_42") (pintype "bidirectional"))
      (node (ref "IC11") (pin "5") (pinfunction "VCC_5") (pintype "power_in"))
      (node (ref "IC13") (pin "5") (pinfunction "VCC_5") (pintype "power_in"))
      (node (ref "IC4") (pin "5") (pinfunction "VCC_5") (pintype "passive"))
      (node (ref "IC8") (pin "1") (pinfunction "VBAT_1") (pintype "power_in"))
      (node (ref "IC8") (pin "24") (pinfunction "VDD_24") (pintype "power_in"))
      (node (ref "IC8") (pin "36") (pinfunction "VDD_36") (pintype "power_in"))
      (node (ref "IC8") (pin "48") (pinfunction "VDD_48") (pintype "power_in"))
      (node (ref "IC9") (pin "1") (pinfunction "VCCIO_2_1") (pintype "bidirectional"))
      (node (ref "IC9") (pin "22") (pinfunction "SPI_VCCIO1_22") (pintype "bidirectional"))
      (node (ref "IC9") (pin "24") (pinfunction "VPP_2V5_24") (pintype "bidirectional"))
      (node (ref "IC9") (pin "33") (pinfunction "VCCIO_0_33") (pintype "bidirectional"))
      (node (ref "L15") (pin "2") (pinfunction "2_2") (pintype "passive"))
      (node (ref "R104") (pin "2") (pinfunction "2_2") (pintype "passive"))
      (node (ref "R64") (pin "1") (pinfunction "1_1") (pintype "passive"))
      (node (ref "R89") (pin "1") (pinfunction "1_1") (pintype "passive"))
      (node (ref "R93") (pin "2") (pinfunction "2_2") (pintype "passive"))
    )
    (net (code "89") (name "/VDDUA") (class "Default")
      (node (ref "C111") (pin "2") (pinfunction "2_2") (pintype "passive"))
      (node (ref "C93") (pin "1") (pinfunction "1_1") (pintype "passive"))
      (node (ref "IC8") (pin "9") (pinfunction "VDDA/VREF+_9") (pintype "power_in"))
      (node (ref "L11") (pin "2") (pinfunction "2_2") (pintype "passive"))
      (node (ref "R16") (pin "1") (pinfunction "1_1") (pintype "passive"))
      (node (ref "R35") (pin "1") (pinfunction "1_1") (pintype "passive"))
    )
    (net (code "90") (name "/VDD_AMP") (class "Default")
      (node (ref "C115") (pin "1") (pinfunction "1_1") (pintype "passive"))
      (node (ref "J1") (pin "9") (pinfunction "9_9") (pintype "passive"))
      (node (ref "L16") (pin "1") (pinfunction "1_1") (pintype "passive"))
      (node (ref "L17") (pin "1") (pinfunction "1_1") (pintype "passive"))
    )
    (net (code "91") (name "/VREF") (class "Default")
      (node (ref "C95") (pin "1") (pinfunction "1_1") (pintype "passive"))
      (node (ref "IC10") (pin "62") (pinfunction "VREF_62") (pintype "bidirectional"))
      (node (ref "L10") (pin "1") (pinfunction "1_1") (pintype "passive"))
      (node (ref "L9") (pin "1") (pinfunction "1_1") (pintype "passive"))
    )
    (net (code "92") (name "/VSS_AMP") (class "Default")
      (node (ref "C116") (pin "1") (pinfunction "1_1") (pintype "passive"))
      (node (ref "J1") (pin "13") (pinfunction "13_13") (pintype "passive"))
      (node (ref "L12") (pin "1") (pinfunction "1_1") (pintype "passive"))
      (node (ref "L14") (pin "1") (pinfunction "1_1") (pintype "passive"))
    )
    (net (code "93") (name "AGND") (class "Default")
      (node (ref "C101") (pin "2") (pinfunction "2_2") (pintype "passive"))
      (node (ref "C102") (pin "2") (pinfunction "2_2") (pintype "passive"))
      (node (ref "C103") (pin "2") (pinfunction "2_2") (pintype "passive"))
      (node (ref "C117") (pin "1") (pinfunction "1_1") (pintype "passive"))
      (node (ref "C120") (pin "1") (pinfunction "1_1") (pintype "passive"))
      (node (ref "C125") (pin "1") (pinfunction "1_1") (pintype "passive"))
      (node (ref "C126") (pin "1") (pinfunction "1_1") (pintype "passive"))
      (node (ref "C128") (pin "1") (pinfunction "1_1") (pintype "passive"))
      (node (ref "C134") (pin "2") (pinfunction "2_2") (pintype "passive"))
      (node (ref "C135") (pin "2") (pinfunction "2_2") (pintype "passive"))
      (node (ref "C52") (pin "1") (pinfunction "1_1") (pintype "passive"))
      (node (ref "C53") (pin "2") (pinfunction "2_2") (pintype "passive"))
      (node (ref "C54") (pin "2") (pinfunction "2_2") (pintype "passive"))
      (node (ref "C56") (pin "2") (pinfunction "2_2") (pintype "passive"))
      (node (ref "C57") (pin "2") (pinfunction "2_2") (pintype "passive"))
      (node (ref "C60") (pin "2") (pinfunction "2_2") (pintype "passive"))
      (node (ref "C61") (pin "2") (pinfunction "2_2") (pintype "passive"))
      (node (ref "C62") (pin "2") (pinfunction "2_2") (pintype "passive"))
      (node (ref "C65") (pin "2") (pinfunction "2_2") (pintype "passive"))
      (node (ref "C69") (pin "2") (pinfunction "2_2") (pintype "passive"))
      (node (ref "C70") (pin "2") (pinfunction "2_2") (pintype "passive"))
      (node (ref "C71") (pin "2") (pinfunction "2_2") (pintype "passive"))
      (node (ref "C72") (pin "2") (pinfunction "2_2") (pintype "passive"))
      (node (ref "C73") (pin "2") (pinfunction "2_2") (pintype "passive"))
      (node (ref "C74") (pin "2") (pinfunction "2_2") (pintype "passive"))
      (node (ref "C78") (pin "2") (pinfunction "2_2") (pintype "passive"))
      (node (ref "C84") (pin "2") (pinfunction "2_2") (pintype "passive"))
      (node (ref "C86") (pin "2") (pinfunction "2_2") (pintype "passive"))
      (node (ref "C87") (pin "2") (pinfunction "2_2") (pintype "passive"))
      (node (ref "C89") (pin "2") (pinfunction "2_2") (pintype "passive"))
      (node (ref "C90") (pin "2") (pinfunction "2_2") (pintype "passive"))
      (node (ref "C91") (pin "2") (pinfunction "2_2") (pintype "passive"))
      (node (ref "C92") (pin "2") (pinfunction "2_2") (pintype "passive"))
      (node (ref "C95") (pin "2") (pinfunction "2_2") (pintype "passive"))
      (node (ref "C97") (pin "2") (pinfunction "2_2") (pintype "passive"))
      (node (ref "D16") (pin "1") (pinfunction "A1_1") (pintype "passive"))
      (node (ref "IC10") (pin "11") (pinfunction "PAR/-SER_11") (pintype "bidirectional"))
      (node (ref "IC10") (pin "14") (pinfunction "GND_14") (pintype "bidirectional"))
      (node (ref "IC10") (pin "19") (pinfunction "ENC-_19") (pintype "bidirectional"))
      (node (ref "IC10") (pin "3") (pinfunction "GND_3") (pintype "bidirectional"))
      (node (ref "IC10") (pin "6") (pinfunction "GND_6") (pintype "bidirectional"))
      (node (ref "IC10") (pin "PAD") (pinfunction "GND_PAD") (pintype "bidirectional"))
      (node (ref "IC5") (pin "3") (pinfunction "IN+_3") (pintype "input"))
      (node (ref "IC6") (pin "13") (pinfunction "-VS_13") (pintype "power_in"))
      (node (ref "IC6") (pin "14") (pinfunction "-VS_14") (pintype "power_in"))
      (node (ref "IC6") (pin "15") (pinfunction "-VS_15") (pintype "power_in"))
      (node (ref "IC6") (pin "16") (pinfunction "-VS_16") (pintype "power_in"))
      (node (ref "IC6") (pin "EXP") (pinfunction "-VS_EXP") (pintype "bidirectional"))
      (node (ref "IC7") (pin "13") (pinfunction "-VS_13") (pintype "power_in"))
      (node (ref "IC7") (pin "14") (pinfunction "-VS_14") (pintype "power_in"))
      (node (ref "IC7") (pin "15") (pinfunction "-VS_15") (pintype "power_in"))
      (node (ref "IC7") (pin "16") (pinfunction "-VS_16") (pintype "power_in"))
      (node (ref "IC7") (pin "EXP") (pinfunction "-VS_EXP") (pintype "bidirectional"))
      (node (ref "J2") (pin "2") (pinfunction "GND_2") (pintype "power_in"))
      (node (ref "J2") (pin "3") (pinfunction "GND_3") (pintype "power_in"))
      (node (ref "R108") (pin "1") (pinfunction "1_1") (pintype "passive"))
      (node (ref "R57") (pin "2") (pinfunction "2_2") (pintype "passive"))
      (node (ref "R59") (pin "2") (pinfunction "2_2") (pintype "passive"))
      (node (ref "R63") (pin "2") (pinfunction "2_2") (pintype "passive"))
      (node (ref "R75") (pin "1") (pinfunction "1_1") (pintype "passive"))
      (node (ref "R80") (pin "1") (pinfunction "1_1") (pintype "passive"))
      (node (ref "R87") (pin "1") (pinfunction "1_1") (pintype "passive"))
    )
    (net (code "94") (name "GND") (class "Default")
      (node (ref "C1") (pin "1") (pinfunction "1_1") (pintype "passive"))
      (node (ref "C100") (pin "2") (pinfunction "2_2") (pintype "passive"))
      (node (ref "C104") (pin "2") (pinfunction "2_2") (pintype "passive"))
      (node (ref "C105") (pin "2") (pinfunction "2_2") (pintype "passive"))
      (node (ref "C106") (pin "2") (pinfunction "2_2") (pintype "passive"))
      (node (ref "C107") (pin "2") (pinfunction "2_2") (pintype "passive"))
      (node (ref "C108") (pin "2") (pinfunction "2_2") (pintype "passive"))
      (node (ref "C109") (pin "2") (pinfunction "2_2") (pintype "passive"))
      (node (ref "C110") (pin "2") (pinfunction "2_2") (pintype "passive"))
      (node (ref "C111") (pin "1") (pinfunction "1_1") (pintype "passive"))
      (node (ref "C112") (pin "2") (pinfunction "2_2") (pintype "passive"))
      (node (ref "C113") (pin "2") (pinfunction "2_2") (pintype "passive"))
      (node (ref "C114") (pin "2") (pinfunction "2_2") (pintype "passive"))
      (node (ref "C115") (pin "2") (pinfunction "2_2") (pintype "passive"))
      (node (ref "C116") (pin "2") (pinfunction "2_2") (pintype "passive"))
      (node (ref "C118") (pin "2") (pinfunction "2_2") (pintype "passive"))
      (node (ref "C119") (pin "2") (pinfunction "2_2") (pintype "passive"))
      (node (ref "C121") (pin "1") (pinfunction "1_1") (pintype "passive"))
      (node (ref "C122") (pin "2") (pinfunction "2_2") (pintype "passive"))
      (node (ref "C123") (pin "2") (pinfunction "2_2") (pintype "passive"))
      (node (ref "C124") (pin "2") (pinfunction "2_2") (pintype "passive"))
      (node (ref "C127") (pin "2") (pinfunction "2_2") (pintype "passive"))
      (node (ref "C129") (pin "1") (pinfunction "1_1") (pintype "passive"))
      (node (ref "C130") (pin "2") (pinfunction "2_2") (pintype "passive"))
      (node (ref "C131") (pin "1") (pinfunction "1_1") (pintype "passive"))
      (node (ref "C132") (pin "1") (pinfunction "1_1") (pintype "passive"))
      (node (ref "C133") (pin "2") (pinfunction "2_2") (pintype "passive"))
      (node (ref "C18") (pin "2") (pinfunction "2_2") (pintype "passive"))
      (node (ref "C19") (pin "2") (pinfunction "2_2") (pintype "passive"))
      (node (ref "C2") (pin "1") (pinfunction "1_1") (pintype "passive"))
      (node (ref "C20") (pin "2") (pinfunction "2_2") (pintype "passive"))
      (node (ref "C21") (pin "1") (pinfunction "1_1") (pintype "passive"))
      (node (ref "C3") (pin "1") (pinfunction "1_1") (pintype "passive"))
      (node (ref "C34") (pin "2") (pinfunction "2_2") (pintype "passive"))
      (node (ref "C35") (pin "2") (pinfunction "2_2") (pintype "passive"))
      (node (ref "C36") (pin "2") (pinfunction "2_2") (pintype "passive"))
      (node (ref "C37") (pin "1") (pinfunction "1_1") (pintype "passive"))
      (node (ref "C49") (pin "2") (pinfunction "2_2") (pintype "passive"))
      (node (ref "C50") (pin "2") (pinfunction "2_2") (pintype "passive"))
      (node (ref "C51") (pin "2") (pinfunction "2_2") (pintype "passive"))
      (node (ref "C58") (pin "2") (pinfunction "2_2") (pintype "passive"))
      (node (ref "C59") (pin "2") (pinfunction "2_2") (pintype "passive"))
      (node (ref "C64") (pin "1") (pinfunction "1_1") (pintype "passive"))
      (node (ref "C66") (pin "2") (pinfunction "2_2") (pintype "passive"))
      (node (ref "C67") (pin "2") (pinfunction "2_2") (pintype "passive"))
      (node (ref "C85") (pin "2") (pinfunction "2_2") (pintype "passive"))
      (node (ref "C88") (pin "2") (pinfunction "2_2") (pintype "passive"))
      (node (ref "C93") (pin "2") (pinfunction "2_2") (pintype "passive"))
      (node (ref "C94") (pin "2") (pinfunction "2_2") (pintype "passive"))
      (node (ref "C96") (pin "2") (pinfunction "2_2") (pintype "passive"))
      (node (ref "C99") (pin "2") (pinfunction "2_2") (pintype "passive"))
      (node (ref "D2") (pin "2") (pinfunction "C2_2") (pintype "passive"))
      (node (ref "IC1") (pin "2") (pinfunction "GND_2") (pintype "power_in"))
      (node (ref "IC10") (pin "41") (pinfunction "OGND_41") (pintype "bidirectional"))
      (node (ref "IC11") (pin "2") (pinfunction "GND_2") (pintype "power_in"))
      (node (ref "IC12") (pin "2") (pinfunction "GND_2") (pintype "power_in"))
      (node (ref "IC13") (pin "2") (pinfunction "GND_2") (pintype "power_in"))
      (node (ref "IC4") (pin "3") (pinfunction "GND_3") (pintype "passive"))
      (node (ref "IC8") (pin "23") (pinfunction "VSS_23") (pintype "power_in"))
      (node (ref "IC8") (pin "35") (pinfunction "VSS_35") (pintype "power_in"))
      (node (ref "IC8") (pin "47") (pinfunction "VSS_47") (pintype "power_in"))
      (node (ref "IC8") (pin "49") (pinfunction "PAD_49") (pintype "power_in"))
      (node (ref "IC8") (pin "8") (pinfunction "VSSA/VREF-_8") (pintype "power_in"))
      (node (ref "IC9") (pin "PAD") (pinfunction "GND_PAD") (pintype "bidirectional"))
      (node (ref "J1") (pin "1") (pinfunction "1_1") (pintype "passive"))
      (node (ref "J1") (pin "4") (pinfunction "4_4") (pintype "passive"))
      (node (ref "J3") (pin "2") (pinfunction "GND_2") (pintype "power_in"))
      (node (ref "J3") (pin "3") (pinfunction "GND_3") (pintype "power_in"))
      (node (ref "J4") (pin "1") (pinfunction "1_1") (pintype "passive"))
      (node (ref "R104") (pin "1") (pinfunction "1_1") (pintype "passive"))
      (node (ref "R108") (pin "2") (pinfunction "2_2") (pintype "passive"))
      (node (ref "R110") (pin "2") (pinfunction "2_2") (pintype "passive"))
      (node (ref "R2") (pin "1") (pinfunction "1_1") (pintype "passive"))
      (node (ref "R3") (pin "1") (pinfunction "1_1") (pintype "passive"))
      (node (ref "R60") (pin "2") (pinfunction "2_2") (pintype "passive"))
      (node (ref "R95") (pin "2") (pinfunction "2_2") (pintype "passive"))
    )
    (net (code "95") (name "Net-(C4-Pad1)") (class "Default")
      (node (ref "C4") (pin "1") (pinfunction "1_1") (pintype "passive"))
      (node (ref "L3") (pin "2") (pinfunction "2_2") (pintype "passive"))
      (node (ref "R3") (pin "2") (pinfunction "2_2") (pintype "passive"))
    )
    (net (code "96") (name "Net-(C18-Pad1)") (class "Default")
      (node (ref "C18") (pin "1") (pinfunction "1_1") (pintype "passive"))
      (node (ref "C4") (pin "2") (pinfunction "2_2") (pintype "passive"))
      (node (ref "L2") (pin "2") (pinfunction "2_2") (pintype "passive"))
    )
    (net (code "97") (name "Net-(C19-Pad1)") (class "Default")
      (node (ref "C19") (pin "1") (pinfunction "1_1") (pintype "passive"))
      (node (ref "L4") (pin "2") (pinfunction "2_2") (pintype "passive"))
      (node (ref "L5") (pin "2") (pinfunction "2_2") (pintype "passive"))
    )
    (net (code "98") (name "Net-(C35-Pad1)") (class "Default")
      (node (ref "C35") (pin "1") (pinfunction "1_1") (pintype "passive"))
      (node (ref "R30") (pin "2") (pinfunction "2_2") (pintype "passive"))
      (node (ref "R31") (pin "1") (pinfunction "1_1") (pintype "passive"))
    )
    (net (code "99") (name "Net-(C36-Pad1)") (class "Default")
      (node (ref "C36") (pin "1") (pinfunction "1_1") (pintype "passive"))
      (node (ref "R31") (pin "2") (pinfunction "2_2") (pintype "passive"))
      (node (ref "R32") (pin "1") (pinfunction "1_1") (pintype "passive"))
    )
    (net (code "100") (name "Net-(C37-Pad2)") (class "Default")
      (node (ref "C37") (pin "2") (pinfunction "2_2") (pintype "passive"))
      (node (ref "C38") (pin "1") (pinfunction "1_1") (pintype "passive"))
      (node (ref "R17") (pin "2") (pinfunction "2_2") (pintype "passive"))
      (node (ref "R38") (pin "2") (pinfunction "2_2") (pintype "passive"))
      (node (ref "R39") (pin "1") (pinfunction "1_1") (pintype "passive"))
    )
    (net (code "101") (name "Net-(C38-Pad2)") (class "Default")
      (node (ref "C38") (pin "2") (pinfunction "2_2") (pintype "passive"))
      (node (ref "R18") (pin "2") (pinfunction "2_2") (pintype "passive"))
      (node (ref "R40") (pin "1") (pinfunction "1_1") (pintype "passive"))
    )
    (net (code "102") (name "Net-(C39-Pad1)") (class "Default")
      (node (ref "C39") (pin "1") (pinfunction "1_1") (pintype "passive"))
      (node (ref "C49") (pin "1") (pinfunction "1_1") (pintype "passive"))
      (node (ref "R19") (pin "2") (pinfunction "2_2") (pintype "passive"))
      (node (ref "R41") (pin "1") (pinfunction "1_1") (pintype "passive"))
    )
    (net (code "103") (name "Net-(C39-Pad2)") (class "Default")
      (node (ref "C39") (pin "2") (pinfunction "2_2") (pintype "passive"))
      (node (ref "C40") (pin "1") (pinfunction "1_1") (pintype "passive"))
      (node (ref "R20") (pin "2") (pinfunction "2_2") (pintype "passive"))
      (node (ref "R48") (pin "1") (pinfunction "1_1") (pintype "passive"))
    )
    (net (code "104") (name "Net-(C46-Pad2)") (class "Default")
      (node (ref "C46") (pin "2") (pinfunction "2_2") (pintype "passive"))
      (node (ref "C47") (pin "1") (pinfunction "1_1") (pintype "passive"))
      (node (ref "R27") (pin "2") (pinfunction "2_2") (pintype "passive"))
    )
    (net (code "105") (name "Net-(C47-Pad2)") (class "Default")
      (node (ref "C47") (pin "2") (pinfunction "2_2") (pintype "passive"))
      (node (ref "C48") (pin "1") (pinfunction "1_1") (pintype "passive"))
      (node (ref "R28") (pin "2") (pinfunction "2_2") (pintype "passive"))
    )
    (net (code "106") (name "Net-(C51-Pad1)") (class "Default")
      (node (ref "C51") (pin "1") (pinfunction "1_1") (pintype "passive"))
      (node (ref "R36") (pin "2") (pinfunction "2_2") (pintype "passive"))
      (node (ref "R37") (pin "1") (pinfunction "1_1") (pintype "passive"))
    )
    (net (code "107") (name "Net-(C52-Pad2)") (class "Default")
      (node (ref "C52") (pin "2") (pinfunction "2_2") (pintype "passive"))
      (node (ref "R39") (pin "2") (pinfunction "2_2") (pintype "passive"))
      (node (ref "R45") (pin "1") (pinfunction "1_1") (pintype "passive"))
    )
    (net (code "108") (name "Net-(C53-Pad1)") (class "Default")
      (node (ref "C53") (pin "1") (pinfunction "1_1") (pintype "passive"))
      (node (ref "R40") (pin "2") (pinfunction "2_2") (pintype "passive"))
      (node (ref "R46") (pin "1") (pinfunction "1_1") (pintype "passive"))
    )
    (net (code "109") (name "Net-(C54-Pad1)") (class "Default")
      (node (ref "C54") (pin "1") (pinfunction "1_1") (pintype "passive"))
      (node (ref "R41") (pin "2") (pinfunction "2_2") (pintype "passive"))
      (node (ref "R47") (pin "1") (pinfunction "1_1") (pintype "passive"))
    )
    (net (code "110") (name "Net-(C60-Pad1)") (class "Default")
      (node (ref "C60") (pin "1") (pinfunction "1_1") (pintype "passive"))
      (node (ref "R49") (pin "2") (pinfunction "2_2") (pintype "passive"))
      (node (ref "R51") (pin "1") (pinfunction "1_1") (pintype "passive"))
    )
    (net (code "111") (name "Net-(C76-Pad1)") (class "Default")
      (node (ref "C76") (pin "1") (pinfunction "1_1") (pintype "passive"))
      (node (ref "R67") (pin "1") (pinfunction "1_1") (pintype "passive"))
      (node (ref "R68") (pin "2") (pinfunction "2_2") (pintype "passive"))
      (node (ref "R69") (pin "1") (pinfunction "1_1") (pintype "passive"))
    )
    (net (code "112") (name "Net-(C76-Pad2)") (class "Default")
      (node (ref "C76") (pin "2") (pinfunction "2_2") (pintype "passive"))
      (node (ref "R72") (pin "2") (pinfunction "2_2") (pintype "passive"))
      (node (ref "R73") (pin "1") (pinfunction "1_1") (pintype "passive"))
      (node (ref "R80") (pin "2") (pinfunction "2_2") (pintype "passive"))
      (node (ref "R81") (pin "1") (pinfunction "1_1") (pintype "passive"))
    )
    (net (code "113") (name "Net-(C78-Pad1)") (class "Default")
      (node (ref "C78") (pin "1") (pinfunction "1_1") (pintype "passive"))
      (node (ref "L9") (pin "2") (pinfunction "2_2") (pintype "passive"))
      (node (ref "R72") (pin "1") (pinfunction "1_1") (pintype "passive"))
    )
    (net (code "114") (name "Net-(C81-Pad1)") (class "Default")
      (node (ref "C81") (pin "1") (pinfunction "1_1") (pintype "passive"))
      (node (ref "R71") (pin "1") (pinfunction "1_1") (pintype "passive"))
      (node (ref "R77") (pin "2") (pinfunction "2_2") (pintype "passive"))
      (node (ref "R78") (pin "1") (pinfunction "1_1") (pintype "passive"))
    )
    (net (code "115") (name "Net-(C81-Pad2)") (class "Default")
      (node (ref "C81") (pin "2") (pinfunction "2_2") (pintype "passive"))
      (node (ref "R83") (pin "2") (pinfunction "2_2") (pintype "passive"))
      (node (ref "R84") (pin "1") (pinfunction "1_1") (pintype "passive"))
      (node (ref "R86") (pin "1") (pinfunction "1_1") (pintype "passive"))
      (node (ref "R87") (pin "2") (pinfunction "2_2") (pintype "passive"))
    )
    (net (code "116") (name "Net-(C84-Pad1)") (class "Default")
      (node (ref "C84") (pin "1") (pinfunction "1_1") (pintype "passive"))
      (node (ref "L10") (pin "2") (pinfunction "2_2") (pintype "passive"))
      (node (ref "R83") (pin "1") (pinfunction "1_1") (pintype "passive"))
    )
    (net (code "117") (name "Net-(C97-Pad1)") (class "Default")
      (node (ref "C97") (pin "1") (pinfunction "1_1") (pintype "passive"))
      (node (ref "C98") (pin "1") (pinfunction "1_1") (pintype "passive"))
      (node (ref "IC10") (pin "10") (pinfunction "REFL_10") (pintype "bidirectional"))
      (node (ref "IC10") (pin "8") (pinfunction "REFL_8") (pintype "bidirectional"))
    )
    (net (code "118") (name "Net-(C101-Pad1)") (class "Default")
      (node (ref "C101") (pin "1") (pinfunction "1_1") (pintype "passive"))
      (node (ref "C98") (pin "2") (pinfunction "2_2") (pintype "passive"))
      (node (ref "IC10") (pin "7") (pinfunction "REFH_7") (pintype "bidirectional"))
      (node (ref "IC10") (pin "9") (pinfunction "REFH_9") (pintype "bidirectional"))
    )
    (net (code "119") (name "Net-(C136-Pad1)") (class "Default")
      (node (ref "C136") (pin "1") (pinfunction "1_1") (pintype "passive"))
      (node (ref "R58") (pin "1") (pinfunction "1_1") (pintype "passive"))
      (node (ref "R60") (pin "1") (pinfunction "1_1") (pintype "passive"))
    )
    (net (code "120") (name "Net-(C137-Pad2)") (class "Default")
      (node (ref "C137") (pin "2") (pinfunction "2_2") (pintype "passive"))
      (node (ref "R76") (pin "2") (pinfunction "2_2") (pintype "passive"))
    )
    (net (code "121") (name "Net-(D1-P$1)") (class "Default")
      (node (ref "D1") (pin "C") (pinfunction "P$1_C") (pintype "bidirectional"))
      (node (ref "R2") (pin "2") (pinfunction "2_2") (pintype "passive"))
    )
    (net (code "122") (name "Net-(D1-P$2)") (class "Default")
      (node (ref "C21") (pin "2") (pinfunction "2_2") (pintype "passive"))
      (node (ref "C22") (pin "1") (pinfunction "1_1") (pintype "passive"))
      (node (ref "D1") (pin "A") (pinfunction "P$2_A") (pintype "bidirectional"))
      (node (ref "D2") (pin "1") (pinfunction "A1_1") (pintype "passive"))
      (node (ref "D3") (pin "2") (pinfunction "C2_2") (pintype "passive"))
      (node (ref "R17") (pin "1") (pinfunction "1_1") (pintype "passive"))
      (node (ref "R32") (pin "2") (pinfunction "2_2") (pintype "passive"))
      (node (ref "R4") (pin "1") (pinfunction "1_1") (pintype "passive"))
    )
    (net (code "123") (name "Net-(D2-C1A2)") (class "Default")
      (node (ref "C5") (pin "2") (pinfunction "2_2") (pintype "passive"))
      (node (ref "C6") (pin "1") (pinfunction "1_1") (pintype "passive"))
      (node (ref "D2") (pin "3") (pinfunction "C1A2_3") (pintype "passive"))
    )
    (net (code "124") (name "Net-(D3-A1)") (class "Default")
      (node (ref "C22") (pin "2") (pinfunction "2_2") (pintype "passive"))
      (node (ref "C23") (pin "1") (pinfunction "1_1") (pintype "passive"))
      (node (ref "D3") (pin "1") (pinfunction "A1_1") (pintype "passive"))
      (node (ref "D4") (pin "2") (pinfunction "C2_2") (pintype "passive"))
      (node (ref "R18") (pin "1") (pinfunction "1_1") (pintype "passive"))
      (node (ref "R4") (pin "2") (pinfunction "2_2") (pintype "passive"))
      (node (ref "R5") (pin "1") (pinfunction "1_1") (pintype "passive"))
    )
    (net (code "125") (name "Net-(D3-C1A2)") (class "Default")
      (node (ref "C6") (pin "2") (pinfunction "2_2") (pintype "passive"))
      (node (ref "C7") (pin "1") (pinfunction "1_1") (pintype "passive"))
      (node (ref "D3") (pin "3") (pinfunction "C1A2_3") (pintype "passive"))
    )
    (net (code "126") (name "Net-(D4-A1)") (class "Default")
      (node (ref "C23") (pin "2") (pinfunction "2_2") (pintype "passive"))
      (node (ref "C24") (pin "1") (pinfunction "1_1") (pintype "passive"))
      (node (ref "D4") (pin "1") (pinfunction "A1_1") (pintype "passive"))
      (node (ref "D5") (pin "2") (pinfunction "C2_2") (pintype "passive"))
      (node (ref "R19") (pin "1") (pinfunction "1_1") (pintype "passive"))
      (node (ref "R5") (pin "2") (pinfunction "2_2") (pintype "passive"))
      (node (ref "R6") (pin "1") (pinfunction "1_1") (pintype "passive"))
    )
    (net (code "127") (name "Net-(D4-C1A2)") (class "Default")
      (node (ref "C7") (pin "2") (pinfunction "2_2") (pintype "passive"))
      (node (ref "C8") (pin "1") (pinfunction "1_1") (pintype "passive"))
      (node (ref "D4") (pin "3") (pinfunction "C1A2_3") (pintype "passive"))
    )
    (net (code "128") (name "Net-(D5-A1)") (class "Default")
      (node (ref "C24") (pin "2") (pinfunction "2_2") (pintype "passive"))
      (node (ref "C25") (pin "1") (pinfunction "1_1") (pintype "passive"))
      (node (ref "D5") (pin "1") (pinfunction "A1_1") (pintype "passive"))
      (node (ref "D6") (pin "2") (pinfunction "C2_2") (pintype "passive"))
      (node (ref "R20") (pin "1") (pinfunction "1_1") (pintype "passive"))
      (node (ref "R6") (pin "2") (pinfunction "2_2") (pintype "passive"))
      (node (ref "R7") (pin "1") (pinfunction "1_1") (pintype "passive"))
    )
    (net (code "129") (name "Net-(D5-C1A2)") (class "Default")
      (node (ref "C8") (pin "2") (pinfunction "2_2") (pintype "passive"))
      (node (ref "C9") (pin "1") (pinfunction "1_1") (pintype "passive"))
      (node (ref "D5") (pin "3") (pinfunction "C1A2_3") (pintype "passive"))
    )
    (net (code "130") (name "Net-(D6-A1)") (class "Default")
      (node (ref "C25") (pin "2") (pinfunction "2_2") (pintype "passive"))
      (node (ref "C26") (pin "1") (pinfunction "1_1") (pintype "passive"))
      (node (ref "D6") (pin "1") (pinfunction "A1_1") (pintype "passive"))
      (node (ref "D7") (pin "2") (pinfunction "C2_2") (pintype "passive"))
      (node (ref "R21") (pin "1") (pinfunction "1_1") (pintype "passive"))
      (node (ref "R7") (pin "2") (pinfunction "2_2") (pintype "passive"))
      (node (ref "R8") (pin "1") (pinfunction "1_1") (pintype "passive"))
    )
    (net (code "131") (name "Net-(D6-C1A2)") (class "Default")
      (node (ref "C10") (pin "1") (pinfunction "1_1") (pintype "passive"))
      (node (ref "C9") (pin "2") (pinfunction "2_2") (pintype "passive"))
      (node (ref "D6") (pin "3") (pinfunction "C1A2_3") (pintype "passive"))
    )
    (net (code "132") (name "Net-(D7-A1)") (class "Default")
      (node (ref "C26") (pin "2") (pinfunction "2_2") (pintype "passive"))
      (node (ref "C27") (pin "1") (pinfunction "1_1") (pintype "passive"))
      (node (ref "D7") (pin "1") (pinfunction "A1_1") (pintype "passive"))
      (node (ref "D8") (pin "2") (pinfunction "C2_2") (pintype "passive"))
      (node (ref "R22") (pin "1") (pinfunction "1_1") (pintype "passive"))
      (node (ref "R8") (pin "2") (pinfunction "2_2") (pintype "passive"))
      (node (ref "R9") (pin "1") (pinfunction "1_1") (pintype "passive"))
    )
    (net (code "133") (name "Net-(D7-C1A2)") (class "Default")
      (node (ref "C10") (pin "2") (pinfunction "2_2") (pintype "passive"))
      (node (ref "C11") (pin "1") (pinfunction "1_1") (pintype "passive"))
      (node (ref "D7") (pin "3") (pinfunction "C1A2_3") (pintype "passive"))
    )
    (net (code "134") (name "Net-(D8-A1)") (class "Default")
      (node (ref "C27") (pin "2") (pinfunction "2_2") (pintype "passive"))
      (node (ref "C28") (pin "1") (pinfunction "1_1") (pintype "passive"))
      (node (ref "D8") (pin "1") (pinfunction "A1_1") (pintype "passive"))
      (node (ref "D9") (pin "2") (pinfunction "C2_2") (pintype "passive"))
      (node (ref "R10") (pin "1") (pinfunction "1_1") (pintype "passive"))
      (node (ref "R23") (pin "1") (pinfunction "1_1") (pintype "passive"))
      (node (ref "R9") (pin "2") (pinfunction "2_2") (pintype "passive"))
    )
    (net (code "135") (name "Net-(D8-C1A2)") (class "Default")
      (node (ref "C11") (pin "2") (pinfunction "2_2") (pintype "passive"))
      (node (ref "C12") (pin "1") (pinfunction "1_1") (pintype "passive"))
      (node (ref "D8") (pin "3") (pinfunction "C1A2_3") (pintype "passive"))
    )
    (net (code "136") (name "Net-(D9-C1A2)") (class "Default")
      (node (ref "C12") (pin "2") (pinfunction "2_2") (pintype "passive"))
      (node (ref "C13") (pin "1") (pinfunction "1_1") (pintype "passive"))
      (node (ref "D9") (pin "3") (pinfunction "C1A2_3") (pintype "passive"))
    )
    (net (code "137") (name "Net-(D10-A1)") (class "Default")
      (node (ref "C29") (pin "2") (pinfunction "2_2") (pintype "passive"))
      (node (ref "C30") (pin "1") (pinfunction "1_1") (pintype "passive"))
      (node (ref "D10") (pin "1") (pinfunction "A1_1") (pintype "passive"))
      (node (ref "D11") (pin "2") (pinfunction "C2_2") (pintype "passive"))
      (node (ref "R11") (pin "2") (pinfunction "2_2") (pintype "passive"))
      (node (ref "R12") (pin "1") (pinfunction "1_1") (pintype "passive"))
      (node (ref "R25") (pin "1") (pinfunction "1_1") (pintype "passive"))
    )
    (net (code "138") (name "Net-(D10-C1A2)") (class "Default")
      (node (ref "C13") (pin "2") (pinfunction "2_2") (pintype "passive"))
      (node (ref "C14") (pin "1") (pinfunction "1_1") (pintype "passive"))
      (node (ref "D10") (pin "3") (pinfunction "C1A2_3") (pintype "passive"))
    )
    (net (code "139") (name "Net-(D10-C2)") (class "Default")
      (node (ref "C28") (pin "2") (pinfunction "2_2") (pintype "passive"))
      (node (ref "C29") (pin "1") (pinfunction "1_1") (pintype "passive"))
      (node (ref "D10") (pin "2") (pinfunction "C2_2") (pintype "passive"))
      (node (ref "D9") (pin "1") (pinfunction "A1_1") (pintype "passive"))
      (node (ref "R10") (pin "2") (pinfunction "2_2") (pintype "passive"))
      (node (ref "R11") (pin "1") (pinfunction "1_1") (pintype "passive"))
      (node (ref "R24") (pin "1") (pinfunction "1_1") (pintype "passive"))
    )
    (net (code "140") (name "Net-(D11-A1)") (class "Default")
      (node (ref "C30") (pin "2") (pinfunction "2_2") (pintype "passive"))
      (node (ref "C31") (pin "1") (pinfunction "1_1") (pintype "passive"))
      (node (ref "D11") (pin "1") (pinfunction "A1_1") (pintype "passive"))
      (node (ref "D12") (pin "2") (pinfunction "C2_2") (pintype "passive"))
      (node (ref "R12") (pin "2") (pinfunction "2_2") (pintype "passive"))
      (node (ref "R13") (pin "1") (pinfunction "1_1") (pintype "passive"))
      (node (ref "R26") (pin "1") (pinfunction "1_1") (pintype "passive"))
    )
    (net (code "141") (name "Net-(D11-C1A2)") (class "Default")
      (node (ref "C14") (pin "2") (pinfunction "2_2") (pintype "passive"))
      (node (ref "C15") (pin "1") (pinfunction "1_1") (pintype "passive"))
      (node (ref "D11") (pin "3") (pinfunction "C1A2_3") (pintype "passive"))
    )
    (net (code "142") (name "Net-(D12-A1)") (class "Default")
      (node (ref "C31") (pin "2") (pinfunction "2_2") (pintype "passive"))
      (node (ref "C32") (pin "1") (pinfunction "1_1") (pintype "passive"))
      (node (ref "D12") (pin "1") (pinfunction "A1_1") (pintype "passive"))
      (node (ref "D13") (pin "2") (pinfunction "C2_2") (pintype "passive"))
      (node (ref "R13") (pin "2") (pinfunction "2_2") (pintype "passive"))
      (node (ref "R14") (pin "1") (pinfunction "1_1") (pintype "passive"))
      (node (ref "R27") (pin "1") (pinfunction "1_1") (pintype "passive"))
    )
    (net (code "143") (name "Net-(D12-C1A2)") (class "Default")
      (node (ref "C15") (pin "2") (pinfunction "2_2") (pintype "passive"))
      (node (ref "C16") (pin "1") (pinfunction "1_1") (pintype "passive"))
      (node (ref "D12") (pin "3") (pinfunction "C1A2_3") (pintype "passive"))
    )
    (net (code "144") (name "Net-(D13-A1)") (class "Default")
      (node (ref "C32") (pin "2") (pinfunction "2_2") (pintype "passive"))
      (node (ref "C33") (pin "1") (pinfunction "1_1") (pintype "passive"))
      (node (ref "D13") (pin "1") (pinfunction "A1_1") (pintype "passive"))
      (node (ref "D14") (pin "2") (pinfunction "C2_2") (pintype "passive"))
      (node (ref "R14") (pin "2") (pinfunction "2_2") (pintype "passive"))
      (node (ref "R15") (pin "1") (pinfunction "1_1") (pintype "passive"))
      (node (ref "R28") (pin "1") (pinfunction "1_1") (pintype "passive"))
    )
    (net (code "145") (name "Net-(D13-C1A2)") (class "Default")
      (node (ref "C16") (pin "2") (pinfunction "2_2") (pintype "passive"))
      (node (ref "C17") (pin "1") (pinfunction "1_1") (pintype "passive"))
      (node (ref "D13") (pin "3") (pinfunction "C1A2_3") (pintype "passive"))
    )
    (net (code "146") (name "Net-(D14-A1)") (class "Default")
      (node (ref "C33") (pin "2") (pinfunction "2_2") (pintype "passive"))
      (node (ref "D14") (pin "1") (pinfunction "A1_1") (pintype "passive"))
      (node (ref "R15") (pin "2") (pinfunction "2_2") (pintype "passive"))
      (node (ref "R29") (pin "1") (pinfunction "1_1") (pintype "passive"))
    )
    (net (code "147") (name "Net-(D14-C1A2)") (class "Default")
      (node (ref "C17") (pin "2") (pinfunction "2_2") (pintype "passive"))
      (node (ref "D14") (pin "3") (pinfunction "C1A2_3") (pintype "passive"))
    )
    (net (code "148") (name "Net-(DY1-P)") (class "Default")
      (node (ref "C45") (pin "2") (pinfunction "2_2") (pintype "passive"))
      (node (ref "C46") (pin "1") (pinfunction "1_1") (pintype "passive"))
      (node (ref "DY1") (pin "P$1") (pinfunction "P_P$1") (pintype "passive"))
      (node (ref "R26") (pin "2") (pinfunction "2_2") (pintype "passive"))
    )
    (net (code "149") (name "Net-(DY2-P)") (class "Default")
      (node (ref "C44") (pin "2") (pinfunction "2_2") (pintype "passive"))
      (node (ref "C45") (pin "1") (pinfunction "1_1") (pintype "passive"))
      (node (ref "DY2") (pin "P$1") (pinfunction "P_P$1") (pintype "passive"))
      (node (ref "R25") (pin "2") (pinfunction "2_2") (pintype "passive"))
    )
    (net (code "150") (name "Net-(DY3-P)") (class "Default")
      (node (ref "C43") (pin "2") (pinfunction "2_2") (pintype "passive"))
      (node (ref "C44") (pin "1") (pinfunction "1_1") (pintype "passive"))
      (node (ref "DY3") (pin "P$1") (pinfunction "P_P$1") (pintype "passive"))
      (node (ref "R24") (pin "2") (pinfunction "2_2") (pintype "passive"))
    )
    (net (code "151") (name "Net-(DY4-P)") (class "Default")
      (node (ref "C42") (pin "2") (pinfunction "2_2") (pintype "passive"))
      (node (ref "C43") (pin "1") (pinfunction "1_1") (pintype "passive"))
      (node (ref "DY4") (pin "P$1") (pinfunction "P_P$1") (pintype "passive"))
      (node (ref "R23") (pin "2") (pinfunction "2_2") (pintype "passive"))
    )
    (net (code "152") (name "Net-(DY5-P)") (class "Default")
      (node (ref "C41") (pin "2") (pinfunction "2_2") (pintype "passive"))
      (node (ref "C42") (pin "1") (pinfunction "1_1") (pintype "passive"))
      (node (ref "DY5") (pin "P$1") (pinfunction "P_P$1") (pintype "passive"))
      (node (ref "R22") (pin "2") (pinfunction "2_2") (pintype "passive"))
    )
    (net (code "153") (name "Net-(DY6-P)") (class "Default")
      (node (ref "C40") (pin "2") (pinfunction "2_2") (pintype "passive"))
      (node (ref "C41") (pin "1") (pinfunction "1_1") (pintype "passive"))
      (node (ref "DY6") (pin "P$1") (pinfunction "P_P$1") (pintype "passive"))
      (node (ref "R21") (pin "2") (pinfunction "2_2") (pintype "passive"))
    )
    (net (code "154") (name "Net-(DY7-P)") (class "Default")
      (node (ref "DY7") (pin "P$1") (pinfunction "P_P$1") (pintype "passive"))
      (node (ref "R48") (pin "2") (pinfunction "2_2") (pintype "passive"))
    )
    (net (code "155") (name "Net-(DY8-P)") (class "Default")
      (node (ref "C55") (pin "1") (pinfunction "1_1") (pintype "passive"))
      (node (ref "DY8") (pin "P$1") (pinfunction "P_P$1") (pintype "passive"))
      (node (ref "R47") (pin "2") (pinfunction "2_2") (pintype "passive"))
    )
    (net (code "156") (name "Net-(DY9-P)") (class "Default")
      (node (ref "DY9") (pin "P$1") (pinfunction "P_P$1") (pintype "passive"))
      (node (ref "R46") (pin "2") (pinfunction "2_2") (pintype "passive"))
    )
    (net (code "157") (name "Net-(DY10-P)") (class "Default")
      (node (ref "DY10") (pin "P$1") (pinfunction "P_P$1") (pintype "passive"))
      (node (ref "R45") (pin "2") (pinfunction "2_2") (pintype "passive"))
    )
    (net (code "158") (name "Net-(IC1-B)") (class "Default")
      (node (ref "IC1") (pin "4") (pinfunction "B_4") (pintype "bidirectional"))
      (node (ref "L2") (pin "1") (pinfunction "1_1") (pintype "passive"))
    )
    (net (code "159") (name "Net-(IC1-VCCB)") (class "Default")
      (node (ref "C1") (pin "2") (pinfunction "2_2") (pintype "passive"))
      (node (ref "C2") (pin "2") (pinfunction "2_2") (pintype "passive"))
      (node (ref "IC1") (pin "6") (pinfunction "VCCB_6") (pintype "power_in"))
      (node (ref "L1") (pin "1") (pinfunction "1_1") (pintype "passive"))
    )
    (net (code "160") (name "Net-(IC2-IN-)") (class "Default")
      (node (ref "C68") (pin "1") (pinfunction "1_1") (pintype "passive"))
      (node (ref "IC2") (pin "4") (pinfunction "IN-_4") (pintype "input"))
      (node (ref "R56") (pin "1") (pinfunction "1_1") (pintype "passive"))
      (node (ref "R59") (pin "1") (pinfunction "1_1") (pintype "passive"))
    )
    (net (code "161") (name "Net-(IC3-QBAR)") (class "Default")
      (node (ref "IC3") (pin "8") (pinfunction "QBAR_8") (pintype "output"))
      (node (ref "R54") (pin "1") (pinfunction "1_1") (pintype "passive"))
    )
    (net (code "162") (name "Net-(IC4-IN)") (class "Default")
      (node (ref "IC4") (pin "2") (pinfunction "IN_2") (pintype "passive"))
      (node (ref "R50") (pin "1") (pinfunction "1_1") (pintype "passive"))
      (node (ref "R54") (pin "2") (pinfunction "2_2") (pintype "passive"))
    )
    (net (code "163") (name "Net-(IC4-OUT)") (class "Default")
      (node (ref "IC4") (pin "4") (pinfunction "OUT_4") (pintype "passive"))
      (node (ref "R42") (pin "1") (pinfunction "1_1") (pintype "passive"))
      (node (ref "R55") (pin "1") (pinfunction "1_1") (pintype "passive"))
    )
    (net (code "164") (name "Net-(IC5-IN-)") (class "Default")
      (node (ref "C63") (pin "1") (pinfunction "1_1") (pintype "passive"))
      (node (ref "IC5") (pin "4") (pinfunction "IN-_4") (pintype "input"))
      (node (ref "R52") (pin "2") (pinfunction "2_2") (pintype "passive"))
      (node (ref "R53") (pin "1") (pinfunction "1_1") (pintype "passive"))
      (node (ref "R57") (pin "1") (pinfunction "1_1") (pintype "passive"))
    )
    (net (code "165") (name "Net-(IC6-+FB)") (class "Default")
      (node (ref "C80") (pin "2") (pinfunction "2_2") (pintype "passive"))
      (node (ref "IC6") (pin "4") (pinfunction "+FB_4") (pintype "output"))
      (node (ref "R81") (pin "2") (pinfunction "2_2") (pintype "passive"))
    )
    (net (code "166") (name "Net-(IC6-+IN)") (class "Default")
      (node (ref "C75") (pin "2") (pinfunction "2_2") (pintype "passive"))
      (node (ref "IC6") (pin "2") (pinfunction "+IN_2") (pintype "input"))
      (node (ref "R69") (pin "2") (pinfunction "2_2") (pintype "passive"))
    )
    (net (code "167") (name "Net-(IC6-+OUT)") (class "Default")
      (node (ref "IC6") (pin "10") (pinfunction "+OUT_10") (pintype "output"))
      (node (ref "R74") (pin "1") (pinfunction "1_1") (pintype "passive"))
    )
    (net (code "168") (name "Net-(IC6--FB)") (class "Default")
      (node (ref "C75") (pin "1") (pinfunction "1_1") (pintype "passive"))
      (node (ref "IC6") (pin "1") (pinfunction "-FB_1") (pintype "output"))
      (node (ref "R67") (pin "2") (pinfunction "2_2") (pintype "passive"))
    )
    (net (code "169") (name "Net-(IC6--IN)") (class "Default")
      (node (ref "C80") (pin "1") (pinfunction "1_1") (pintype "passive"))
      (node (ref "IC6") (pin "3") (pinfunction "-IN_3") (pintype "output"))
      (node (ref "R73") (pin "2") (pinfunction "2_2") (pintype "passive"))
    )
    (net (code "170") (name "Net-(IC6--OUT)") (class "Default")
      (node (ref "IC6") (pin "11") (pinfunction "-OUT_11") (pintype "output"))
      (node (ref "R70") (pin "1") (pinfunction "1_1") (pintype "passive"))
    )
    (net (code "171") (name "Net-(IC7-+FB)") (class "Default")
      (node (ref "C83") (pin "2") (pinfunction "2_2") (pintype "passive"))
      (node (ref "IC7") (pin "4") (pinfunction "+FB_4") (pintype "output"))
      (node (ref "R86") (pin "2") (pinfunction "2_2") (pintype "passive"))
    )
    (net (code "172") (name "Net-(IC7-+IN)") (class "Default")
      (node (ref "C79") (pin "2") (pinfunction "2_2") (pintype "passive"))
      (node (ref "IC7") (pin "2") (pinfunction "+IN_2") (pintype "input"))
      (node (ref "R78") (pin "2") (pinfunction "2_2") (pintype "passive"))
    )
    (net (code "173") (name "Net-(IC7-+OUT)") (class "Default")
      (node (ref "IC7") (pin "10") (pinfunction "+OUT_10") (pintype "output"))
      (node (ref "R85") (pin "1") (pinfunction "1_1") (pintype "passive"))
    )
    (net (code "174") (name "Net-(IC7--FB)") (class "Default")
      (node (ref "C79") (pin "1") (pinfunction "1_1") (pintype "passive"))
      (node (ref "IC7") (pin "1") (pinfunction "-FB_1") (pintype "output"))
      (node (ref "R71") (pin "2") (pinfunction "2_2") (pintype "passive"))
    )
    (net (code "175") (name "Net-(IC7--IN)") (class "Default")
      (node (ref "C83") (pin "1") (pinfunction "1_1") (pintype "passive"))
      (node (ref "IC7") (pin "3") (pinfunction "-IN_3") (pintype "output"))
      (node (ref "R84") (pin "2") (pinfunction "2_2") (pintype "passive"))
    )
    (net (code "176") (name "Net-(IC7--OUT)") (class "Default")
      (node (ref "IC7") (pin "11") (pinfunction "-OUT_11") (pintype "output"))
      (node (ref "R79") (pin "1") (pinfunction "1_1") (pintype "passive"))
    )
    (net (code "177") (name "Net-(IC8-NRST)") (class "Default")
      (node (ref "C94") (pin "1") (pinfunction "1_1") (pintype "passive"))
      (node (ref "IC8") (pin "7") (pinfunction "NRST_7") (pintype "input"))
    )
    (net (code "178") (name "Net-(IC8-PA2)") (class "Default")
      (node (ref "IC8") (pin "12") (pinfunction "PA2_12") (pintype "bidirectional"))
      (node (ref "R92") (pin "2") (pinfunction "2_2") (pintype "passive"))
    )
    (net (code "179") (name "Net-(IC8-PH3{slash}BOOT0)") (class "Default")
      (node (ref "IC8") (pin "44") (pinfunction "PH3/BOOT0_44") (pintype "bidirectional"))
      (node (ref "R64") (pin "2") (pinfunction "2_2") (pintype "passive"))
      (node (ref "R65") (pin "1") (pinfunction "1_1") (pintype "passive"))
    )
    (net (code "180") (name "Net-(IC9-VCCPLL)") (class "Default")
      (node (ref "C108") (pin "1") (pinfunction "1_1") (pintype "passive"))
      (node (ref "C109") (pin "1") (pinfunction "1_1") (pintype "passive"))
      (node (ref "IC9") (pin "29") (pinfunction "VCCPLL_29") (pintype "bidirectional"))
      (node (ref "R94") (pin "2") (pinfunction "2_2") (pintype "passive"))
    )
    (net (code "181") (name "Net-(IC11-1Y)") (class "Default")
      (node (ref "C113") (pin "1") (pinfunction "1_1") (pintype "passive"))
      (node (ref "IC11") (pin "6") (pinfunction "1Y_6") (pintype "output"))
      (node (ref "R98") (pin "2") (pinfunction "2_2") (pintype "passive"))
    )
    (net (code "182") (name "Net-(IC11-2Y)") (class "Default")
      (node (ref "C112") (pin "1") (pinfunction "1_1") (pintype "passive"))
      (node (ref "IC11") (pin "4") (pinfunction "2Y_4") (pintype "output"))
      (node (ref "R99") (pin "2") (pinfunction "2_2") (pintype "passive"))
    )
    (net (code "183") (name "Net-(IC12-IN-)") (class "Default")
      (node (ref "IC12") (pin "5") (pinfunction "IN-_5") (pintype "bidirectional"))
      (node (ref "L13") (pin "1") (pinfunction "1_1") (pintype "passive"))
      (node (ref "R101") (pin "1") (pinfunction "1_1") (pintype "passive"))
    )
    (net (code "184") (name "Net-(IC12-OUT)") (class "Default")
      (node (ref "IC12") (pin "6") (pinfunction "OUT_6") (pintype "output"))
      (node (ref "R111") (pin "2") (pinfunction "2_2") (pintype "passive"))
    )
    (net (code "185") (name "Net-(IC13-1Y)") (class "Default")
      (node (ref "C124") (pin "1") (pinfunction "1_1") (pintype "passive"))
      (node (ref "IC13") (pin "6") (pinfunction "1Y_6") (pintype "output"))
      (node (ref "R34") (pin "2") (pinfunction "2_2") (pintype "passive"))
    )
    (net (code "186") (name "Net-(IC13-2Y)") (class "Default")
      (node (ref "C123") (pin "1") (pinfunction "1_1") (pintype "passive"))
      (node (ref "IC13") (pin "4") (pinfunction "2Y_4") (pintype "output"))
      (node (ref "R33") (pin "2") (pinfunction "2_2") (pintype "passive"))
    )
    (net (code "187") (name "Net-(J2-SIGNAL)") (class "Default")
      (node (ref "C137") (pin "1") (pinfunction "1_1") (pintype "passive"))
      (node (ref "J2") (pin "1") (pinfunction "SIGNAL_1") (pintype "passive"))
    )
    (net (code "188") (name "Net-(J3-SIGNAL)") (class "Default")
      (node (ref "C136") (pin "2") (pinfunction "2_2") (pintype "passive"))
      (node (ref "J3") (pin "1") (pinfunction "SIGNAL_1") (pintype "passive"))
    )
    (net (code "189") (name "Net-(K-P)") (class "Default")
      (node (ref "C48") (pin "2") (pinfunction "2_2") (pintype "passive"))
      (node (ref "K") (pin "P$1") (pinfunction "P_P$1") (pintype "passive"))
      (node (ref "R29") (pin "2") (pinfunction "2_2") (pintype "passive"))
    )
    (net (code "190") (name "Net-(L1-Pad2)") (class "Default")
      (node (ref "L1") (pin "2") (pinfunction "2_2") (pintype "passive"))
      (node (ref "R1") (pin "2") (pinfunction "2_2") (pintype "passive"))
    )
    (net (code "191") (name "Net-(L3-Pad1)") (class "Default")
      (node (ref "L3") (pin "1") (pinfunction "1_1") (pintype "passive"))
      (node (ref "L4") (pin "1") (pinfunction "1_1") (pintype "passive"))
    )
    (net (code "192") (name "Net-(L5-Pad1)") (class "Default")
      (node (ref "L5") (pin "1") (pinfunction "1_1") (pintype "passive"))
      (node (ref "L6") (pin "2") (pinfunction "2_2") (pintype "passive"))
    )
    (net (code "193") (name "Net-(R37-Pad2)") (class "Default")
      (node (ref "R37") (pin "2") (pinfunction "2_2") (pintype "passive"))
      (node (ref "R38") (pin "1") (pinfunction "1_1") (pintype "passive"))
    )
    (net (code "194") (name "unconnected-(IC3-Q-Pad7)") (class "Default")
      (node (ref "IC3") (pin "7") (pinfunction "Q_7") (pintype "output"))
    )
    (net (code "195") (name "unconnected-(IC4-NC-Pad1)") (class "Default")
      (node (ref "IC4") (pin "1") (pinfunction "NC_1") (pintype "no_connect"))
    )
    (net (code "196") (name "unconnected-(IC8-PA1-Pad11)") (class "Default")
      (node (ref "IC8") (pin "11") (pinfunction "PA1_11") (pintype "bidirectional"))
    )
    (net (code "197") (name "unconnected-(IC8-PA6-Pad16)") (class "Default")
      (node (ref "IC8") (pin "16") (pinfunction "PA6_16") (pintype "bidirectional"))
    )
    (net (code "198") (name "unconnected-(IC8-PA13-Pad34)") (class "Default")
      (node (ref "IC8") (pin "34") (pinfunction "PA13_34") (pintype "bidirectional"))
    )
    (net (code "199") (name "unconnected-(IC8-PA14-Pad37)") (class "Default")
      (node (ref "IC8") (pin "37") (pinfunction "PA14_37") (pintype "bidirectional"))
    )
    (net (code "200") (name "unconnected-(IC8-PA15-Pad38)") (class "Default")
      (node (ref "IC8") (pin "38") (pinfunction "PA15_38") (pintype "bidirectional"))
    )
    (net (code "201") (name "unconnected-(IC8-PB2-Pad20)") (class "Default")
      (node (ref "IC8") (pin "20") (pinfunction "PB2_20") (pintype "bidirectional"))
    )
    (net (code "202") (name "unconnected-(IC8-PB6-Pad42)") (class "Default")
      (node (ref "IC8") (pin "42") (pinfunction "PB6_42") (pintype "bidirectional"))
    )
    (net (code "203") (name "unconnected-(IC8-PB8-Pad45)") (class "Default")
      (node (ref "IC8") (pin "45") (pinfunction "PB8_45") (pintype "bidirectional"))
    )
    (net (code "204") (name "unconnected-(IC8-PB9-Pad46)") (class "Default")
      (node (ref "IC8") (pin "46") (pinfunction "PB9_46") (pintype "bidirectional"))
    )
    (net (code "205") (name "unconnected-(IC8-PC13-Pad2)") (class "Default")
      (node (ref "IC8") (pin "2") (pinfunction "PC13_2") (pintype "bidirectional"))
    )
    (net (code "206") (name "unconnected-(IC8-PC14-OSC32_IN-Pad3)") (class "Default")
      (node (ref "IC8") (pin "3") (pinfunction "PC14-OSC32_IN_3") (pintype "bidirectional"))
    )
    (net (code "207") (name "unconnected-(IC8-PC15-OSC32_OUT-Pad4)") (class "Default")
      (node (ref "IC8") (pin "4") (pinfunction "PC15-OSC32_OUT_4") (pintype "bidirectional"))
    )
    (net (code "208") (name "unconnected-(IC8-PH1-OSC_OUT-Pad6)") (class "Default")
      (node (ref "IC8") (pin "6") (pinfunction "PH1-OSC_OUT_6") (pintype "bidirectional"))
    )
    (net (code "209") (name "unconnected-(IC9-RGB0-Pad39)") (class "Default")
      (node (ref "IC9") (pin "39") (pinfunction "RGB0_39") (pintype "bidirectional"))
    )
    (net (code "210") (name "unconnected-(IC9-RGB1-Pad40)") (class "Default")
      (node (ref "IC9") (pin "40") (pinfunction "RGB1_40") (pintype "bidirectional"))
    )
    (net (code "211") (name "unconnected-(IC9-RGB2-Pad41)") (class "Default")
      (node (ref "IC9") (pin "41") (pinfunction "RGB2_41") (pintype "bidirectional"))
    )
    (net (code "212") (name "unconnected-(IC10-CLKOUT--Pad39)") (class "Default")
      (node (ref "IC10") (pin "39") (pinfunction "CLKOUT-_39") (pintype "bidirectional"))
    )
    (net (code "213") (name "unconnected-(IC10-DNC-Pad23)") (class "Default")
      (node (ref "IC10") (pin "23") (pinfunction "DNC_23") (pintype "bidirectional"))
    )
    (net (code "214") (name "unconnected-(IC10-DNC-Pad24)") (class "Default")
      (node (ref "IC10") (pin "24") (pinfunction "DNC_24") (pintype "bidirectional"))
    )
    (net (code "215") (name "unconnected-(IC10-DNC-Pad25)") (class "Default")
      (node (ref "IC10") (pin "25") (pinfunction "DNC_25") (pintype "bidirectional"))
    )
    (net (code "216") (name "unconnected-(IC10-DNC-Pad26)") (class "Default")
      (node (ref "IC10") (pin "26") (pinfunction "DNC_26") (pintype "bidirectional"))
    )
    (net (code "217") (name "unconnected-(IC10-DNC-Pad43)") (class "Default")
      (node (ref "IC10") (pin "43") (pinfunction "DNC_43") (pintype "bidirectional"))
    )
    (net (code "218") (name "unconnected-(IC10-DNC-Pad44)") (class "Default")
      (node (ref "IC10") (pin "44") (pinfunction "DNC_44") (pintype "bidirectional"))
    )
    (net (code "219") (name "unconnected-(IC10-DNC-Pad45)") (class "Default")
      (node (ref "IC10") (pin "45") (pinfunction "DNC_45") (pintype "bidirectional"))
    )
    (net (code "220") (name "unconnected-(IC10-DNC-Pad46)") (class "Default")
      (node (ref "IC10") (pin "46") (pinfunction "DNC_46") (pintype "bidirectional"))
    )
    (net (code "221") (name "unconnected-(IC10-OF1-Pad60)") (class "Default")
      (node (ref "IC10") (pin "60") (pinfunction "OF1_60") (pintype "bidirectional"))
    )
    (net (code "222") (name "unconnected-(IC10-OF2-Pad59)") (class "Default")
      (node (ref "IC10") (pin "59") (pinfunction "OF2_59") (pintype "bidirectional"))
    )
  )
)
